# PCB-Tester-Relay-Board.net
KiCad netlist of a schematic drawn in Altium Designer
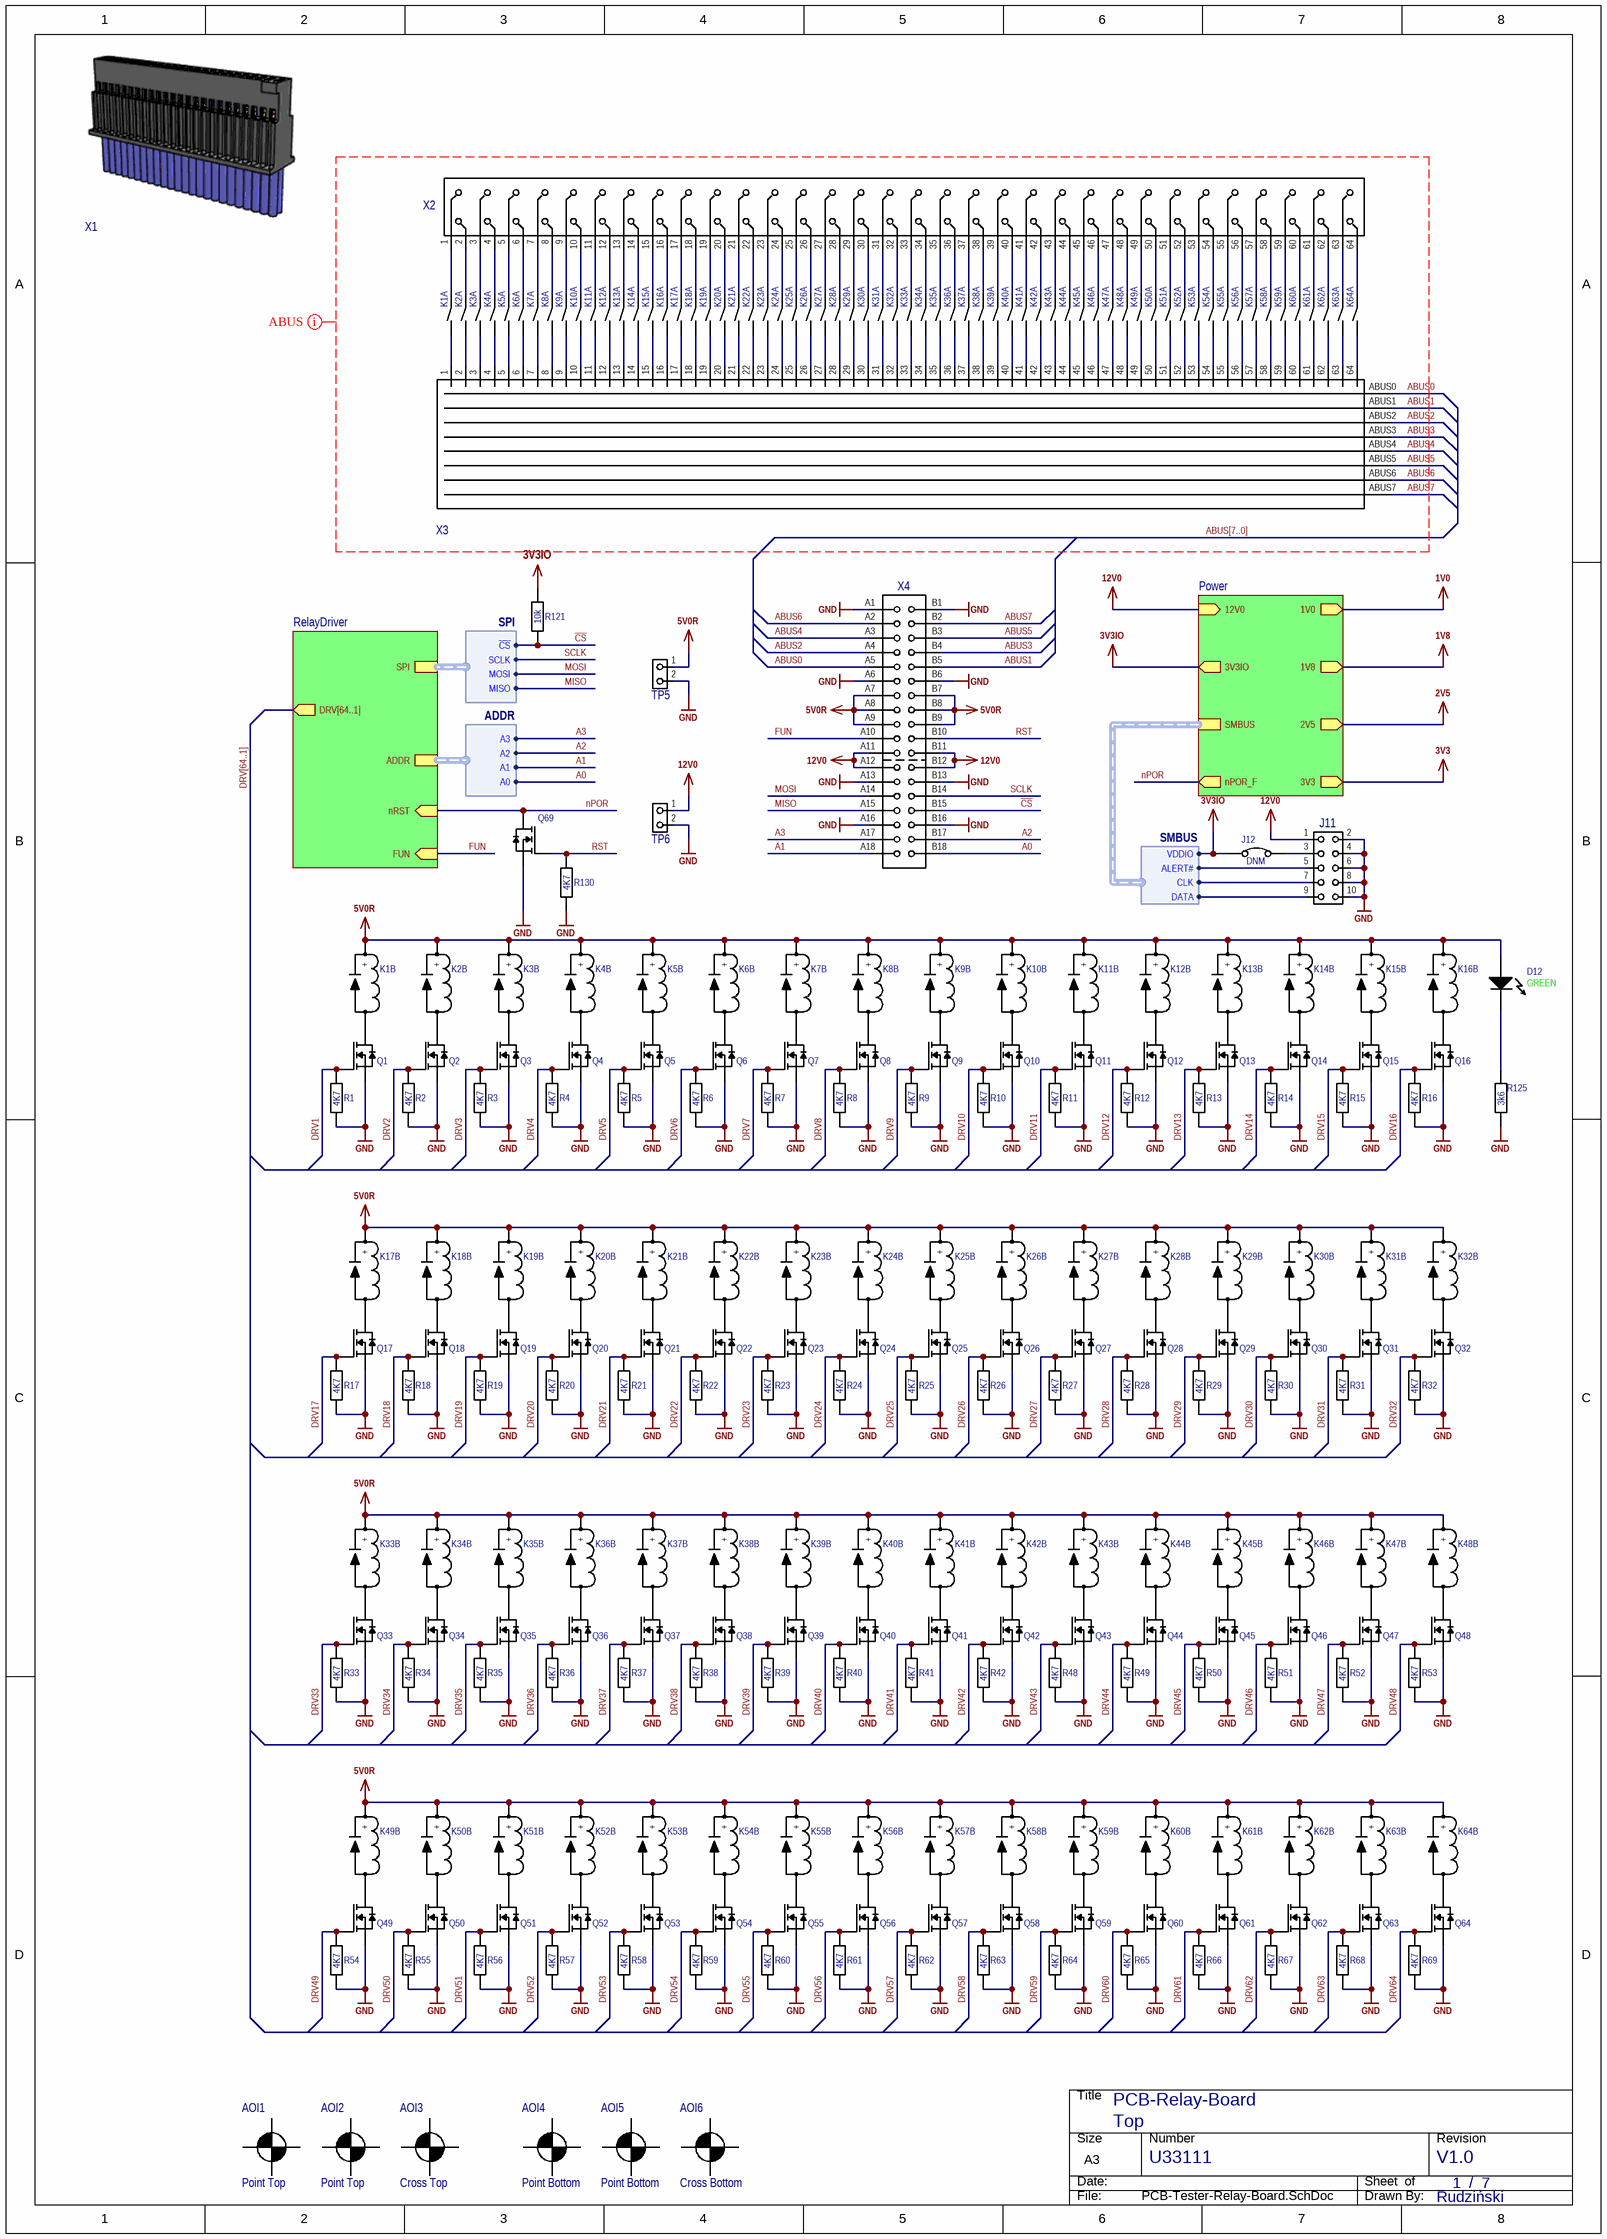
[diagram p0: PCB-Tester-Relay-Board.SchDoc]

(export (version "E")
  (design (tool "Eeschema 10.0.6"))
  (components
    (comp (ref "AOI1")
      (value "AOI")
      (footprint "Fiducial Point")
      (description "Assembly AOI")
      (fields (field (name "SHAPE") "Point Top") (field (name "13. CREATED DATE/NAME") "AUG2018/Hören"))
      (libsource (lib "chickenfood") (part "Fiducial"))
    )
    (comp (ref "AOI2")
      (value "AOI")
      (footprint "Fiducial Point")
      (description "Assembly AOI")
      (fields (field (name "SHAPE") "Point Top") (field (name "13. CREATED DATE/NAME") "AUG2018/Hören"))
      (libsource (lib "chickenfood") (part "Fiducial"))
    )
    (comp (ref "AOI3")
      (value "AOI")
      (footprint "Fiducial Cross")
      (description "Assembly AOI")
      (fields (field (name "SHAPE") "Cross Top") (field (name "13. CREATED DATE/NAME") "AUG2018/Hören"))
      (libsource (lib "chickenfood") (part "Fiducial"))
    )
    (comp (ref "AOI4")
      (value "AOI")
      (footprint "Fiducial Point")
      (description "Assembly AOI")
      (fields (field (name "SHAPE") "Point Bottom") (field (name "13. CREATED DATE/NAME") "AUG2018/Hören"))
      (libsource (lib "chickenfood") (part "Fiducial"))
    )
    (comp (ref "AOI5")
      (value "AOI")
      (footprint "Fiducial Point")
      (description "Assembly AOI")
      (fields (field (name "SHAPE") "Point Bottom") (field (name "13. CREATED DATE/NAME") "AUG2018/Hören"))
      (libsource (lib "chickenfood") (part "Fiducial"))
    )
    (comp (ref "AOI6")
      (value "AOI")
      (footprint "Fiducial Cross")
      (description "Assembly AOI")
      (fields (field (name "SHAPE") "Cross Bottom") (field (name "13. CREATED DATE/NAME") "AUG2018/Hören"))
      (libsource (lib "chickenfood") (part "Fiducial"))
    )
    (comp (ref "D12")
      (value "D")
      (footprint "L0603G")
      (description "LED GREEN DIFFUSED 0603 SMD")
      (fields
        (field (name "02. DISTRIBUTOR PART NUMBER") "475-2709-6-ND")
        (field (name "07. MANUFACTURER  PART NUMBER") "LG L29K-G2J1-24-Z")
        (field (name "COLOR") "GREEN")
        (field (name "13. CREATED DATE/NAME") "AUG2018/Hören")
      )
      (libsource (lib "chickenfood") (part "LED"))
    )
    (comp (ref "J11")
      (value "J")
      (footprint "Header 100mil 5x2")
      (description ".100\" High-Temp Variable Post Height Terminal Strip")
      (fields
        (field (name "02. DISTRIBUTOR PART NUMBER") "HMTSW-105-07-G-D-240")
        (field (name "13. CREATED DATE/NAME") "AUG2018/Hören")
      )
      (libsource (lib "PCB-Tester-Board-V1") (part "Header 5x2Pins 100mil"))
    )
    (comp (ref "J12")
      (value "DNM")
      (footprint "JumperSMD")
      (description "RES SMD 0 OHM JUMPER 1/10W 0603")
      (fields
        (field (name "02. DISTRIBUTOR PART NUMBER") "311-0.0GRDKR-ND")
        (field (name "07. MANUFACTURER  PART NUMBER") "RC0603JR-070RL")
      )
      (libsource (lib "chickenfood") (part "Jumper SMD"))
    )
    (comp (ref "K1")
      (value "K")
      (footprint "118-1A")
      (description "5V Signal Relais, Normal Open")
      (fields
        (field (name "02. DISTRIBUTOR PART NUMBER") "118-1-A-5/2D")
        (field (name "13. CREATED DATE/NAME") "20.12.17 S. Kaiser")
      )
      (libsource (lib "chickenfood") (part "118-1-A-5/2D"))
    )
    (comp (ref "K2")
      (value "K")
      (footprint "118-1A")
      (description "5V Signal Relais, Normal Open")
      (fields
        (field (name "02. DISTRIBUTOR PART NUMBER") "118-1-A-5/2D")
        (field (name "13. CREATED DATE/NAME") "20.12.17 S. Kaiser")
      )
      (libsource (lib "chickenfood") (part "118-1-A-5/2D"))
    )
    (comp (ref "K3")
      (value "K")
      (footprint "118-1A")
      (description "5V Signal Relais, Normal Open")
      (fields
        (field (name "02. DISTRIBUTOR PART NUMBER") "118-1-A-5/2D")
        (field (name "13. CREATED DATE/NAME") "20.12.17 S. Kaiser")
      )
      (libsource (lib "chickenfood") (part "118-1-A-5/2D"))
    )
    (comp (ref "K4")
      (value "K")
      (footprint "118-1A")
      (description "5V Signal Relais, Normal Open")
      (fields
        (field (name "02. DISTRIBUTOR PART NUMBER") "118-1-A-5/2D")
        (field (name "13. CREATED DATE/NAME") "20.12.17 S. Kaiser")
      )
      (libsource (lib "chickenfood") (part "118-1-A-5/2D"))
    )
    (comp (ref "K5")
      (value "K")
      (footprint "118-1A")
      (description "5V Signal Relais, Normal Open")
      (fields
        (field (name "02. DISTRIBUTOR PART NUMBER") "118-1-A-5/2D")
        (field (name "13. CREATED DATE/NAME") "20.12.17 S. Kaiser")
      )
      (libsource (lib "chickenfood") (part "118-1-A-5/2D"))
    )
    (comp (ref "K6")
      (value "K")
      (footprint "118-1A")
      (description "5V Signal Relais, Normal Open")
      (fields
        (field (name "02. DISTRIBUTOR PART NUMBER") "118-1-A-5/2D")
        (field (name "13. CREATED DATE/NAME") "20.12.17 S. Kaiser")
      )
      (libsource (lib "") (part "118-1-A-5/2D_1"))
    )
    (comp (ref "K7")
      (value "K")
      (footprint "118-1A")
      (description "5V Signal Relais, Normal Open")
      (fields
        (field (name "02. DISTRIBUTOR PART NUMBER") "118-1-A-5/2D")
        (field (name "13. CREATED DATE/NAME") "20.12.17 S. Kaiser")
      )
      (libsource (lib "chickenfood") (part "118-1-A-5/2D"))
    )
    (comp (ref "K8")
      (value "K")
      (footprint "118-1A")
      (description "5V Signal Relais, Normal Open")
      (fields
        (field (name "02. DISTRIBUTOR PART NUMBER") "118-1-A-5/2D")
        (field (name "13. CREATED DATE/NAME") "20.12.17 S. Kaiser")
      )
      (libsource (lib "chickenfood") (part "118-1-A-5/2D"))
    )
    (comp (ref "K9")
      (value "K")
      (footprint "118-1A")
      (description "5V Signal Relais, Normal Open")
      (fields
        (field (name "02. DISTRIBUTOR PART NUMBER") "118-1-A-5/2D")
        (field (name "13. CREATED DATE/NAME") "20.12.17 S. Kaiser")
      )
      (libsource (lib "") (part "118-1-A-5/2D_1"))
    )
    (comp (ref "K10")
      (value "K")
      (footprint "118-1A")
      (description "5V Signal Relais, Normal Open")
      (fields
        (field (name "02. DISTRIBUTOR PART NUMBER") "118-1-A-5/2D")
        (field (name "13. CREATED DATE/NAME") "20.12.17 S. Kaiser")
      )
      (libsource (lib "") (part "118-1-A-5/2D_1"))
    )
    (comp (ref "K11")
      (value "K")
      (footprint "118-1A")
      (description "5V Signal Relais, Normal Open")
      (fields
        (field (name "02. DISTRIBUTOR PART NUMBER") "118-1-A-5/2D")
        (field (name "13. CREATED DATE/NAME") "20.12.17 S. Kaiser")
      )
      (libsource (lib "chickenfood") (part "118-1-A-5/2D"))
    )
    (comp (ref "K12")
      (value "K")
      (footprint "118-1A")
      (description "5V Signal Relais, Normal Open")
      (fields
        (field (name "02. DISTRIBUTOR PART NUMBER") "118-1-A-5/2D")
        (field (name "13. CREATED DATE/NAME") "20.12.17 S. Kaiser")
      )
      (libsource (lib "chickenfood") (part "118-1-A-5/2D"))
    )
    (comp (ref "K13")
      (value "K")
      (footprint "118-1A")
      (description "5V Signal Relais, Normal Open")
      (fields
        (field (name "02. DISTRIBUTOR PART NUMBER") "118-1-A-5/2D")
        (field (name "13. CREATED DATE/NAME") "20.12.17 S. Kaiser")
      )
      (libsource (lib "") (part "118-1-A-5/2D_1"))
    )
    (comp (ref "K14")
      (value "K")
      (footprint "118-1A")
      (description "5V Signal Relais, Normal Open")
      (fields
        (field (name "02. DISTRIBUTOR PART NUMBER") "118-1-A-5/2D")
        (field (name "13. CREATED DATE/NAME") "20.12.17 S. Kaiser")
      )
      (libsource (lib "") (part "118-1-A-5/2D_1"))
    )
    (comp (ref "K15")
      (value "K")
      (footprint "118-1A")
      (description "5V Signal Relais, Normal Open")
      (fields
        (field (name "02. DISTRIBUTOR PART NUMBER") "118-1-A-5/2D")
        (field (name "13. CREATED DATE/NAME") "20.12.17 S. Kaiser")
      )
      (libsource (lib "chickenfood") (part "118-1-A-5/2D"))
    )
    (comp (ref "K16")
      (value "K")
      (footprint "118-1A")
      (description "5V Signal Relais, Normal Open")
      (fields
        (field (name "02. DISTRIBUTOR PART NUMBER") "118-1-A-5/2D")
        (field (name "13. CREATED DATE/NAME") "20.12.17 S. Kaiser")
      )
      (libsource (lib "") (part "118-1-A-5/2D_1"))
    )
    (comp (ref "K17")
      (value "K")
      (footprint "118-1A")
      (description "5V Signal Relais, Normal Open")
      (fields
        (field (name "02. DISTRIBUTOR PART NUMBER") "118-1-A-5/2D")
        (field (name "13. CREATED DATE/NAME") "20.12.17 S. Kaiser")
      )
      (libsource (lib "") (part "118-1-A-5/2D_1"))
    )
    (comp (ref "K18")
      (value "K")
      (footprint "118-1A")
      (description "5V Signal Relais, Normal Open")
      (fields
        (field (name "02. DISTRIBUTOR PART NUMBER") "118-1-A-5/2D")
        (field (name "13. CREATED DATE/NAME") "20.12.17 S. Kaiser")
      )
      (libsource (lib "") (part "118-1-A-5/2D_1"))
    )
    (comp (ref "K19")
      (value "K")
      (footprint "118-1A")
      (description "5V Signal Relais, Normal Open")
      (fields
        (field (name "02. DISTRIBUTOR PART NUMBER") "118-1-A-5/2D")
        (field (name "13. CREATED DATE/NAME") "20.12.17 S. Kaiser")
      )
      (libsource (lib "") (part "118-1-A-5/2D_1"))
    )
    (comp (ref "K20")
      (value "K")
      (footprint "118-1A")
      (description "5V Signal Relais, Normal Open")
      (fields
        (field (name "02. DISTRIBUTOR PART NUMBER") "118-1-A-5/2D")
        (field (name "13. CREATED DATE/NAME") "20.12.17 S. Kaiser")
      )
      (libsource (lib "chickenfood") (part "118-1-A-5/2D"))
    )
    (comp (ref "K21")
      (value "K")
      (footprint "118-1A")
      (description "5V Signal Relais, Normal Open")
      (fields
        (field (name "02. DISTRIBUTOR PART NUMBER") "118-1-A-5/2D")
        (field (name "13. CREATED DATE/NAME") "20.12.17 S. Kaiser")
      )
      (libsource (lib "") (part "118-1-A-5/2D_1"))
    )
    (comp (ref "K22")
      (value "K")
      (footprint "118-1A")
      (description "5V Signal Relais, Normal Open")
      (fields
        (field (name "02. DISTRIBUTOR PART NUMBER") "118-1-A-5/2D")
        (field (name "13. CREATED DATE/NAME") "20.12.17 S. Kaiser")
      )
      (libsource (lib "chickenfood") (part "118-1-A-5/2D"))
    )
    (comp (ref "K23")
      (value "K")
      (footprint "118-1A")
      (description "5V Signal Relais, Normal Open")
      (fields
        (field (name "02. DISTRIBUTOR PART NUMBER") "118-1-A-5/2D")
        (field (name "13. CREATED DATE/NAME") "20.12.17 S. Kaiser")
      )
      (libsource (lib "") (part "118-1-A-5/2D_1"))
    )
    (comp (ref "K24")
      (value "K")
      (footprint "118-1A")
      (description "5V Signal Relais, Normal Open")
      (fields
        (field (name "02. DISTRIBUTOR PART NUMBER") "118-1-A-5/2D")
        (field (name "13. CREATED DATE/NAME") "20.12.17 S. Kaiser")
      )
      (libsource (lib "chickenfood") (part "118-1-A-5/2D"))
    )
    (comp (ref "K25")
      (value "K")
      (footprint "118-1A")
      (description "5V Signal Relais, Normal Open")
      (fields
        (field (name "02. DISTRIBUTOR PART NUMBER") "118-1-A-5/2D")
        (field (name "13. CREATED DATE/NAME") "20.12.17 S. Kaiser")
      )
      (libsource (lib "chickenfood") (part "118-1-A-5/2D"))
    )
    (comp (ref "K26")
      (value "K")
      (footprint "118-1A")
      (description "5V Signal Relais, Normal Open")
      (fields
        (field (name "02. DISTRIBUTOR PART NUMBER") "118-1-A-5/2D")
        (field (name "13. CREATED DATE/NAME") "20.12.17 S. Kaiser")
      )
      (libsource (lib "") (part "118-1-A-5/2D_1"))
    )
    (comp (ref "K27")
      (value "K")
      (footprint "118-1A")
      (description "5V Signal Relais, Normal Open")
      (fields
        (field (name "02. DISTRIBUTOR PART NUMBER") "118-1-A-5/2D")
        (field (name "13. CREATED DATE/NAME") "20.12.17 S. Kaiser")
      )
      (libsource (lib "") (part "118-1-A-5/2D_1"))
    )
    (comp (ref "K28")
      (value "K")
      (footprint "118-1A")
      (description "5V Signal Relais, Normal Open")
      (fields
        (field (name "02. DISTRIBUTOR PART NUMBER") "118-1-A-5/2D")
        (field (name "13. CREATED DATE/NAME") "20.12.17 S. Kaiser")
      )
      (libsource (lib "chickenfood") (part "118-1-A-5/2D"))
    )
    (comp (ref "K29")
      (value "K")
      (footprint "118-1A")
      (description "5V Signal Relais, Normal Open")
      (fields
        (field (name "02. DISTRIBUTOR PART NUMBER") "118-1-A-5/2D")
        (field (name "13. CREATED DATE/NAME") "20.12.17 S. Kaiser")
      )
      (libsource (lib "") (part "118-1-A-5/2D_1"))
    )
    (comp (ref "K30")
      (value "K")
      (footprint "118-1A")
      (description "5V Signal Relais, Normal Open")
      (fields
        (field (name "02. DISTRIBUTOR PART NUMBER") "118-1-A-5/2D")
        (field (name "13. CREATED DATE/NAME") "20.12.17 S. Kaiser")
      )
      (libsource (lib "") (part "118-1-A-5/2D_1"))
    )
    (comp (ref "K31")
      (value "K")
      (footprint "118-1A")
      (description "5V Signal Relais, Normal Open")
      (fields
        (field (name "02. DISTRIBUTOR PART NUMBER") "118-1-A-5/2D")
        (field (name "13. CREATED DATE/NAME") "20.12.17 S. Kaiser")
      )
      (libsource (lib "chickenfood") (part "118-1-A-5/2D"))
    )
    (comp (ref "K32")
      (value "K")
      (footprint "118-1A")
      (description "5V Signal Relais, Normal Open")
      (fields
        (field (name "02. DISTRIBUTOR PART NUMBER") "118-1-A-5/2D")
        (field (name "13. CREATED DATE/NAME") "20.12.17 S. Kaiser")
      )
      (libsource (lib "chickenfood") (part "118-1-A-5/2D"))
    )
    (comp (ref "K33")
      (value "K")
      (footprint "118-1A")
      (description "5V Signal Relais, Normal Open")
      (fields
        (field (name "02. DISTRIBUTOR PART NUMBER") "118-1-A-5/2D")
        (field (name "13. CREATED DATE/NAME") "20.12.17 S. Kaiser")
      )
      (libsource (lib "chickenfood") (part "118-1-A-5/2D"))
    )
    (comp (ref "K34")
      (value "K")
      (footprint "118-1A")
      (description "5V Signal Relais, Normal Open")
      (fields
        (field (name "02. DISTRIBUTOR PART NUMBER") "118-1-A-5/2D")
        (field (name "13. CREATED DATE/NAME") "20.12.17 S. Kaiser")
      )
      (libsource (lib "") (part "118-1-A-5/2D_1"))
    )
    (comp (ref "K35")
      (value "K")
      (footprint "118-1A")
      (description "5V Signal Relais, Normal Open")
      (fields
        (field (name "02. DISTRIBUTOR PART NUMBER") "118-1-A-5/2D")
        (field (name "13. CREATED DATE/NAME") "20.12.17 S. Kaiser")
      )
      (libsource (lib "") (part "118-1-A-5/2D_1"))
    )
    (comp (ref "K36")
      (value "K")
      (footprint "118-1A")
      (description "5V Signal Relais, Normal Open")
      (fields
        (field (name "02. DISTRIBUTOR PART NUMBER") "118-1-A-5/2D")
        (field (name "13. CREATED DATE/NAME") "20.12.17 S. Kaiser")
      )
      (libsource (lib "") (part "118-1-A-5/2D_1"))
    )
    (comp (ref "K37")
      (value "K")
      (footprint "118-1A")
      (description "5V Signal Relais, Normal Open")
      (fields
        (field (name "02. DISTRIBUTOR PART NUMBER") "118-1-A-5/2D")
        (field (name "13. CREATED DATE/NAME") "20.12.17 S. Kaiser")
      )
      (libsource (lib "chickenfood") (part "118-1-A-5/2D"))
    )
    (comp (ref "K38")
      (value "K")
      (footprint "118-1A")
      (description "5V Signal Relais, Normal Open")
      (fields
        (field (name "02. DISTRIBUTOR PART NUMBER") "118-1-A-5/2D")
        (field (name "13. CREATED DATE/NAME") "20.12.17 S. Kaiser")
      )
      (libsource (lib "chickenfood") (part "118-1-A-5/2D"))
    )
    (comp (ref "K39")
      (value "K")
      (footprint "118-1A")
      (description "5V Signal Relais, Normal Open")
      (fields
        (field (name "02. DISTRIBUTOR PART NUMBER") "118-1-A-5/2D")
        (field (name "13. CREATED DATE/NAME") "20.12.17 S. Kaiser")
      )
      (libsource (lib "") (part "118-1-A-5/2D_1"))
    )
    (comp (ref "K40")
      (value "K")
      (footprint "118-1A")
      (description "5V Signal Relais, Normal Open")
      (fields
        (field (name "02. DISTRIBUTOR PART NUMBER") "118-1-A-5/2D")
        (field (name "13. CREATED DATE/NAME") "20.12.17 S. Kaiser")
      )
      (libsource (lib "") (part "118-1-A-5/2D_1"))
    )
    (comp (ref "K41")
      (value "K")
      (footprint "118-1A")
      (description "5V Signal Relais, Normal Open")
      (fields
        (field (name "02. DISTRIBUTOR PART NUMBER") "118-1-A-5/2D")
        (field (name "13. CREATED DATE/NAME") "20.12.17 S. Kaiser")
      )
      (libsource (lib "") (part "118-1-A-5/2D_1"))
    )
    (comp (ref "K42")
      (value "K")
      (footprint "118-1A")
      (description "5V Signal Relais, Normal Open")
      (fields
        (field (name "02. DISTRIBUTOR PART NUMBER") "118-1-A-5/2D")
        (field (name "13. CREATED DATE/NAME") "20.12.17 S. Kaiser")
      )
      (libsource (lib "") (part "118-1-A-5/2D_1"))
    )
    (comp (ref "K43")
      (value "K")
      (footprint "118-1A")
      (description "5V Signal Relais, Normal Open")
      (fields
        (field (name "02. DISTRIBUTOR PART NUMBER") "118-1-A-5/2D")
        (field (name "13. CREATED DATE/NAME") "20.12.17 S. Kaiser")
      )
      (libsource (lib "chickenfood") (part "118-1-A-5/2D"))
    )
    (comp (ref "K44")
      (value "K")
      (footprint "118-1A")
      (description "5V Signal Relais, Normal Open")
      (fields
        (field (name "02. DISTRIBUTOR PART NUMBER") "118-1-A-5/2D")
        (field (name "13. CREATED DATE/NAME") "20.12.17 S. Kaiser")
      )
      (libsource (lib "") (part "118-1-A-5/2D_1"))
    )
    (comp (ref "K45")
      (value "K")
      (footprint "118-1A")
      (description "5V Signal Relais, Normal Open")
      (fields
        (field (name "02. DISTRIBUTOR PART NUMBER") "118-1-A-5/2D")
        (field (name "13. CREATED DATE/NAME") "20.12.17 S. Kaiser")
      )
      (libsource (lib "chickenfood") (part "118-1-A-5/2D"))
    )
    (comp (ref "K46")
      (value "K")
      (footprint "118-1A")
      (description "5V Signal Relais, Normal Open")
      (fields
        (field (name "02. DISTRIBUTOR PART NUMBER") "118-1-A-5/2D")
        (field (name "13. CREATED DATE/NAME") "20.12.17 S. Kaiser")
      )
      (libsource (lib "chickenfood") (part "118-1-A-5/2D"))
    )
    (comp (ref "K47")
      (value "K")
      (footprint "118-1A")
      (description "5V Signal Relais, Normal Open")
      (fields
        (field (name "02. DISTRIBUTOR PART NUMBER") "118-1-A-5/2D")
        (field (name "13. CREATED DATE/NAME") "20.12.17 S. Kaiser")
      )
      (libsource (lib "") (part "118-1-A-5/2D_1"))
    )
    (comp (ref "K48")
      (value "K")
      (footprint "118-1A")
      (description "5V Signal Relais, Normal Open")
      (fields
        (field (name "02. DISTRIBUTOR PART NUMBER") "118-1-A-5/2D")
        (field (name "13. CREATED DATE/NAME") "20.12.17 S. Kaiser")
      )
      (libsource (lib "chickenfood") (part "118-1-A-5/2D"))
    )
    (comp (ref "K49")
      (value "K")
      (footprint "118-1A")
      (description "5V Signal Relais, Normal Open")
      (fields
        (field (name "02. DISTRIBUTOR PART NUMBER") "118-1-A-5/2D")
        (field (name "13. CREATED DATE/NAME") "20.12.17 S. Kaiser")
      )
      (libsource (lib "chickenfood") (part "118-1-A-5/2D"))
    )
    (comp (ref "K50")
      (value "K")
      (footprint "118-1A")
      (description "5V Signal Relais, Normal Open")
      (fields
        (field (name "02. DISTRIBUTOR PART NUMBER") "118-1-A-5/2D")
        (field (name "13. CREATED DATE/NAME") "20.12.17 S. Kaiser")
      )
      (libsource (lib "") (part "118-1-A-5/2D_1"))
    )
    (comp (ref "K51")
      (value "K")
      (footprint "118-1A")
      (description "5V Signal Relais, Normal Open")
      (fields
        (field (name "02. DISTRIBUTOR PART NUMBER") "118-1-A-5/2D")
        (field (name "13. CREATED DATE/NAME") "20.12.17 S. Kaiser")
      )
      (libsource (lib "") (part "118-1-A-5/2D_1"))
    )
    (comp (ref "K52")
      (value "K")
      (footprint "118-1A")
      (description "5V Signal Relais, Normal Open")
      (fields
        (field (name "02. DISTRIBUTOR PART NUMBER") "118-1-A-5/2D")
        (field (name "13. CREATED DATE/NAME") "20.12.17 S. Kaiser")
      )
      (libsource (lib "") (part "118-1-A-5/2D_1"))
    )
    (comp (ref "K53")
      (value "K")
      (footprint "118-1A")
      (description "5V Signal Relais, Normal Open")
      (fields
        (field (name "02. DISTRIBUTOR PART NUMBER") "118-1-A-5/2D")
        (field (name "13. CREATED DATE/NAME") "20.12.17 S. Kaiser")
      )
      (libsource (lib "chickenfood") (part "118-1-A-5/2D"))
    )
    (comp (ref "K54")
      (value "K")
      (footprint "118-1A")
      (description "5V Signal Relais, Normal Open")
      (fields
        (field (name "02. DISTRIBUTOR PART NUMBER") "118-1-A-5/2D")
        (field (name "13. CREATED DATE/NAME") "20.12.17 S. Kaiser")
      )
      (libsource (lib "") (part "118-1-A-5/2D_1"))
    )
    (comp (ref "K55")
      (value "K")
      (footprint "118-1A")
      (description "5V Signal Relais, Normal Open")
      (fields
        (field (name "02. DISTRIBUTOR PART NUMBER") "118-1-A-5/2D")
        (field (name "13. CREATED DATE/NAME") "20.12.17 S. Kaiser")
      )
      (libsource (lib "") (part "118-1-A-5/2D_1"))
    )
    (comp (ref "K56")
      (value "K")
      (footprint "118-1A")
      (description "5V Signal Relais, Normal Open")
      (fields
        (field (name "02. DISTRIBUTOR PART NUMBER") "118-1-A-5/2D")
        (field (name "13. CREATED DATE/NAME") "20.12.17 S. Kaiser")
      )
      (libsource (lib "") (part "118-1-A-5/2D_1"))
    )
    (comp (ref "K57")
      (value "K")
      (footprint "118-1A")
      (description "5V Signal Relais, Normal Open")
      (fields
        (field (name "02. DISTRIBUTOR PART NUMBER") "118-1-A-5/2D")
        (field (name "13. CREATED DATE/NAME") "20.12.17 S. Kaiser")
      )
      (libsource (lib "chickenfood") (part "118-1-A-5/2D"))
    )
    (comp (ref "K58")
      (value "K")
      (footprint "118-1A")
      (description "5V Signal Relais, Normal Open")
      (fields
        (field (name "02. DISTRIBUTOR PART NUMBER") "118-1-A-5/2D")
        (field (name "13. CREATED DATE/NAME") "20.12.17 S. Kaiser")
      )
      (libsource (lib "") (part "118-1-A-5/2D_1"))
    )
    (comp (ref "K59")
      (value "K")
      (footprint "118-1A")
      (description "5V Signal Relais, Normal Open")
      (fields
        (field (name "02. DISTRIBUTOR PART NUMBER") "118-1-A-5/2D")
        (field (name "13. CREATED DATE/NAME") "20.12.17 S. Kaiser")
      )
      (libsource (lib "") (part "118-1-A-5/2D_1"))
    )
    (comp (ref "K60")
      (value "K")
      (footprint "118-1A")
      (description "5V Signal Relais, Normal Open")
      (fields
        (field (name "02. DISTRIBUTOR PART NUMBER") "118-1-A-5/2D")
        (field (name "13. CREATED DATE/NAME") "20.12.17 S. Kaiser")
      )
      (libsource (lib "") (part "118-1-A-5/2D_1"))
    )
    (comp (ref "K61")
      (value "K")
      (footprint "118-1A")
      (description "5V Signal Relais, Normal Open")
      (fields
        (field (name "02. DISTRIBUTOR PART NUMBER") "118-1-A-5/2D")
        (field (name "13. CREATED DATE/NAME") "20.12.17 S. Kaiser")
      )
      (libsource (lib "chickenfood") (part "118-1-A-5/2D"))
    )
    (comp (ref "K62")
      (value "K")
      (footprint "118-1A")
      (description "5V Signal Relais, Normal Open")
      (fields
        (field (name "02. DISTRIBUTOR PART NUMBER") "118-1-A-5/2D")
        (field (name "13. CREATED DATE/NAME") "20.12.17 S. Kaiser")
      )
      (libsource (lib "") (part "118-1-A-5/2D_1"))
    )
    (comp (ref "K63")
      (value "K")
      (footprint "118-1A")
      (description "5V Signal Relais, Normal Open")
      (fields
        (field (name "02. DISTRIBUTOR PART NUMBER") "118-1-A-5/2D")
        (field (name "13. CREATED DATE/NAME") "20.12.17 S. Kaiser")
      )
      (libsource (lib "chickenfood") (part "118-1-A-5/2D"))
    )
    (comp (ref "K64")
      (value "K")
      (footprint "118-1A")
      (description "5V Signal Relais, Normal Open")
      (fields
        (field (name "02. DISTRIBUTOR PART NUMBER") "118-1-A-5/2D")
        (field (name "13. CREATED DATE/NAME") "20.12.17 S. Kaiser")
      )
      (libsource (lib "chickenfood") (part "118-1-A-5/2D"))
    )
    (comp (ref "Q1")
      (value "Q")
      (footprint "SOT23-3")
      (description "MOSFET N-CH 25V 680MA SOT-23")
      (fields
        (field (name "02. DISTRIBUTOR PART NUMBER") "FDV303NDKR-ND")
        (field (name "07. MANUFACTURER  PART NUMBER") "FDV303N")
        (field (name "13. CREATED DATE/NAME") "AUG 2018 / Hören")
      )
      (libsource (lib "SCT8-Board1") (part "FDV303N"))
    )
    (comp (ref "Q2")
      (value "Q")
      (footprint "SOT23-3")
      (description "MOSFET N-CH 25V 680MA SOT-23")
      (fields
        (field (name "02. DISTRIBUTOR PART NUMBER") "FDV303NDKR-ND")
        (field (name "07. MANUFACTURER  PART NUMBER") "FDV303N")
        (field (name "13. CREATED DATE/NAME") "AUG 2018 / Hören")
      )
      (libsource (lib "SCT8-Board1") (part "FDV303N"))
    )
    (comp (ref "Q3")
      (value "Q")
      (footprint "SOT23-3")
      (description "MOSFET N-CH 25V 680MA SOT-23")
      (fields
        (field (name "02. DISTRIBUTOR PART NUMBER") "FDV303NDKR-ND")
        (field (name "07. MANUFACTURER  PART NUMBER") "FDV303N")
        (field (name "13. CREATED DATE/NAME") "AUG 2018 / Hören")
      )
      (libsource (lib "SCT8-Board1") (part "FDV303N"))
    )
    (comp (ref "Q4")
      (value "Q")
      (footprint "SOT23-3")
      (description "MOSFET N-CH 25V 680MA SOT-23")
      (fields
        (field (name "02. DISTRIBUTOR PART NUMBER") "FDV303NDKR-ND")
        (field (name "07. MANUFACTURER  PART NUMBER") "FDV303N")
        (field (name "13. CREATED DATE/NAME") "AUG 2018 / Hören")
      )
      (libsource (lib "SCT8-Board1") (part "FDV303N"))
    )
    (comp (ref "Q5")
      (value "Q")
      (footprint "SOT23-3")
      (description "MOSFET N-CH 25V 680MA SOT-23")
      (fields
        (field (name "02. DISTRIBUTOR PART NUMBER") "FDV303NDKR-ND")
        (field (name "07. MANUFACTURER  PART NUMBER") "FDV303N")
        (field (name "13. CREATED DATE/NAME") "AUG 2018 / Hören")
      )
      (libsource (lib "SCT8-Board1") (part "FDV303N"))
    )
    (comp (ref "Q6")
      (value "Q")
      (footprint "SOT23-3")
      (description "MOSFET N-CH 25V 680MA SOT-23")
      (fields
        (field (name "02. DISTRIBUTOR PART NUMBER") "FDV303NDKR-ND")
        (field (name "07. MANUFACTURER  PART NUMBER") "FDV303N")
        (field (name "13. CREATED DATE/NAME") "AUG 2018 / Hören")
      )
      (libsource (lib "SCT8-Board1") (part "FDV303N"))
    )
    (comp (ref "Q7")
      (value "Q")
      (footprint "SOT23-3")
      (description "MOSFET N-CH 25V 680MA SOT-23")
      (fields
        (field (name "02. DISTRIBUTOR PART NUMBER") "FDV303NDKR-ND")
        (field (name "07. MANUFACTURER  PART NUMBER") "FDV303N")
        (field (name "13. CREATED DATE/NAME") "AUG 2018 / Hören")
      )
      (libsource (lib "SCT8-Board1") (part "FDV303N"))
    )
    (comp (ref "Q8")
      (value "Q")
      (footprint "SOT23-3")
      (description "MOSFET N-CH 25V 680MA SOT-23")
      (fields
        (field (name "02. DISTRIBUTOR PART NUMBER") "FDV303NDKR-ND")
        (field (name "07. MANUFACTURER  PART NUMBER") "FDV303N")
        (field (name "13. CREATED DATE/NAME") "AUG 2018 / Hören")
      )
      (libsource (lib "SCT8-Board1") (part "FDV303N"))
    )
    (comp (ref "Q9")
      (value "Q")
      (footprint "SOT23-3")
      (description "MOSFET N-CH 25V 680MA SOT-23")
      (fields
        (field (name "02. DISTRIBUTOR PART NUMBER") "FDV303NDKR-ND")
        (field (name "07. MANUFACTURER  PART NUMBER") "FDV303N")
        (field (name "13. CREATED DATE/NAME") "AUG 2018 / Hören")
      )
      (libsource (lib "SCT8-Board1") (part "FDV303N"))
    )
    (comp (ref "Q10")
      (value "Q")
      (footprint "SOT23-3")
      (description "MOSFET N-CH 25V 680MA SOT-23")
      (fields
        (field (name "02. DISTRIBUTOR PART NUMBER") "FDV303NDKR-ND")
        (field (name "07. MANUFACTURER  PART NUMBER") "FDV303N")
        (field (name "13. CREATED DATE/NAME") "AUG 2018 / Hören")
      )
      (libsource (lib "SCT8-Board1") (part "FDV303N"))
    )
    (comp (ref "Q11")
      (value "Q")
      (footprint "SOT23-3")
      (description "MOSFET N-CH 25V 680MA SOT-23")
      (fields
        (field (name "02. DISTRIBUTOR PART NUMBER") "FDV303NDKR-ND")
        (field (name "07. MANUFACTURER  PART NUMBER") "FDV303N")
        (field (name "13. CREATED DATE/NAME") "AUG 2018 / Hören")
      )
      (libsource (lib "SCT8-Board1") (part "FDV303N"))
    )
    (comp (ref "Q12")
      (value "Q")
      (footprint "SOT23-3")
      (description "MOSFET N-CH 25V 680MA SOT-23")
      (fields
        (field (name "02. DISTRIBUTOR PART NUMBER") "FDV303NDKR-ND")
        (field (name "07. MANUFACTURER  PART NUMBER") "FDV303N")
        (field (name "13. CREATED DATE/NAME") "AUG 2018 / Hören")
      )
      (libsource (lib "SCT8-Board1") (part "FDV303N"))
    )
    (comp (ref "Q13")
      (value "Q")
      (footprint "SOT23-3")
      (description "MOSFET N-CH 25V 680MA SOT-23")
      (fields
        (field (name "02. DISTRIBUTOR PART NUMBER") "FDV303NDKR-ND")
        (field (name "07. MANUFACTURER  PART NUMBER") "FDV303N")
        (field (name "13. CREATED DATE/NAME") "AUG 2018 / Hören")
      )
      (libsource (lib "SCT8-Board1") (part "FDV303N"))
    )
    (comp (ref "Q14")
      (value "Q")
      (footprint "SOT23-3")
      (description "MOSFET N-CH 25V 680MA SOT-23")
      (fields
        (field (name "02. DISTRIBUTOR PART NUMBER") "FDV303NDKR-ND")
        (field (name "07. MANUFACTURER  PART NUMBER") "FDV303N")
        (field (name "13. CREATED DATE/NAME") "AUG 2018 / Hören")
      )
      (libsource (lib "SCT8-Board1") (part "FDV303N"))
    )
    (comp (ref "Q15")
      (value "Q")
      (footprint "SOT23-3")
      (description "MOSFET N-CH 25V 680MA SOT-23")
      (fields
        (field (name "02. DISTRIBUTOR PART NUMBER") "FDV303NDKR-ND")
        (field (name "07. MANUFACTURER  PART NUMBER") "FDV303N")
        (field (name "13. CREATED DATE/NAME") "AUG 2018 / Hören")
      )
      (libsource (lib "SCT8-Board1") (part "FDV303N"))
    )
    (comp (ref "Q16")
      (value "Q")
      (footprint "SOT23-3")
      (description "MOSFET N-CH 25V 680MA SOT-23")
      (fields
        (field (name "02. DISTRIBUTOR PART NUMBER") "FDV303NDKR-ND")
        (field (name "07. MANUFACTURER  PART NUMBER") "FDV303N")
        (field (name "13. CREATED DATE/NAME") "AUG 2018 / Hören")
      )
      (libsource (lib "SCT8-Board1") (part "FDV303N"))
    )
    (comp (ref "Q17")
      (value "Q")
      (footprint "SOT23-3")
      (description "MOSFET N-CH 25V 680MA SOT-23")
      (fields
        (field (name "02. DISTRIBUTOR PART NUMBER") "FDV303NDKR-ND")
        (field (name "07. MANUFACTURER  PART NUMBER") "FDV303N")
        (field (name "13. CREATED DATE/NAME") "AUG 2018 / Hören")
      )
      (libsource (lib "SCT8-Board1") (part "FDV303N"))
    )
    (comp (ref "Q18")
      (value "Q")
      (footprint "SOT23-3")
      (description "MOSFET N-CH 25V 680MA SOT-23")
      (fields
        (field (name "02. DISTRIBUTOR PART NUMBER") "FDV303NDKR-ND")
        (field (name "07. MANUFACTURER  PART NUMBER") "FDV303N")
        (field (name "13. CREATED DATE/NAME") "AUG 2018 / Hören")
      )
      (libsource (lib "SCT8-Board1") (part "FDV303N"))
    )
    (comp (ref "Q19")
      (value "Q")
      (footprint "SOT23-3")
      (description "MOSFET N-CH 25V 680MA SOT-23")
      (fields
        (field (name "02. DISTRIBUTOR PART NUMBER") "FDV303NDKR-ND")
        (field (name "07. MANUFACTURER  PART NUMBER") "FDV303N")
        (field (name "13. CREATED DATE/NAME") "AUG 2018 / Hören")
      )
      (libsource (lib "SCT8-Board1") (part "FDV303N"))
    )
    (comp (ref "Q20")
      (value "Q")
      (footprint "SOT23-3")
      (description "MOSFET N-CH 25V 680MA SOT-23")
      (fields
        (field (name "02. DISTRIBUTOR PART NUMBER") "FDV303NDKR-ND")
        (field (name "07. MANUFACTURER  PART NUMBER") "FDV303N")
        (field (name "13. CREATED DATE/NAME") "AUG 2018 / Hören")
      )
      (libsource (lib "SCT8-Board1") (part "FDV303N"))
    )
    (comp (ref "Q21")
      (value "Q")
      (footprint "SOT23-3")
      (description "MOSFET N-CH 25V 680MA SOT-23")
      (fields
        (field (name "02. DISTRIBUTOR PART NUMBER") "FDV303NDKR-ND")
        (field (name "07. MANUFACTURER  PART NUMBER") "FDV303N")
        (field (name "13. CREATED DATE/NAME") "AUG 2018 / Hören")
      )
      (libsource (lib "SCT8-Board1") (part "FDV303N"))
    )
    (comp (ref "Q22")
      (value "Q")
      (footprint "SOT23-3")
      (description "MOSFET N-CH 25V 680MA SOT-23")
      (fields
        (field (name "02. DISTRIBUTOR PART NUMBER") "FDV303NDKR-ND")
        (field (name "07. MANUFACTURER  PART NUMBER") "FDV303N")
        (field (name "13. CREATED DATE/NAME") "AUG 2018 / Hören")
      )
      (libsource (lib "SCT8-Board1") (part "FDV303N"))
    )
    (comp (ref "Q23")
      (value "Q")
      (footprint "SOT23-3")
      (description "MOSFET N-CH 25V 680MA SOT-23")
      (fields
        (field (name "02. DISTRIBUTOR PART NUMBER") "FDV303NDKR-ND")
        (field (name "07. MANUFACTURER  PART NUMBER") "FDV303N")
        (field (name "13. CREATED DATE/NAME") "AUG 2018 / Hören")
      )
      (libsource (lib "SCT8-Board1") (part "FDV303N"))
    )
    (comp (ref "Q24")
      (value "Q")
      (footprint "SOT23-3")
      (description "MOSFET N-CH 25V 680MA SOT-23")
      (fields
        (field (name "02. DISTRIBUTOR PART NUMBER") "FDV303NDKR-ND")
        (field (name "07. MANUFACTURER  PART NUMBER") "FDV303N")
        (field (name "13. CREATED DATE/NAME") "AUG 2018 / Hören")
      )
      (libsource (lib "SCT8-Board1") (part "FDV303N"))
    )
    (comp (ref "Q25")
      (value "Q")
      (footprint "SOT23-3")
      (description "MOSFET N-CH 25V 680MA SOT-23")
      (fields
        (field (name "02. DISTRIBUTOR PART NUMBER") "FDV303NDKR-ND")
        (field (name "07. MANUFACTURER  PART NUMBER") "FDV303N")
        (field (name "13. CREATED DATE/NAME") "AUG 2018 / Hören")
      )
      (libsource (lib "SCT8-Board1") (part "FDV303N"))
    )
    (comp (ref "Q26")
      (value "Q")
      (footprint "SOT23-3")
      (description "MOSFET N-CH 25V 680MA SOT-23")
      (fields
        (field (name "02. DISTRIBUTOR PART NUMBER") "FDV303NDKR-ND")
        (field (name "07. MANUFACTURER  PART NUMBER") "FDV303N")
        (field (name "13. CREATED DATE/NAME") "AUG 2018 / Hören")
      )
      (libsource (lib "SCT8-Board1") (part "FDV303N"))
    )
    (comp (ref "Q27")
      (value "Q")
      (footprint "SOT23-3")
      (description "MOSFET N-CH 25V 680MA SOT-23")
      (fields
        (field (name "02. DISTRIBUTOR PART NUMBER") "FDV303NDKR-ND")
        (field (name "07. MANUFACTURER  PART NUMBER") "FDV303N")
        (field (name "13. CREATED DATE/NAME") "AUG 2018 / Hören")
      )
      (libsource (lib "SCT8-Board1") (part "FDV303N"))
    )
    (comp (ref "Q28")
      (value "Q")
      (footprint "SOT23-3")
      (description "MOSFET N-CH 25V 680MA SOT-23")
      (fields
        (field (name "02. DISTRIBUTOR PART NUMBER") "FDV303NDKR-ND")
        (field (name "07. MANUFACTURER  PART NUMBER") "FDV303N")
        (field (name "13. CREATED DATE/NAME") "AUG 2018 / Hören")
      )
      (libsource (lib "SCT8-Board1") (part "FDV303N"))
    )
    (comp (ref "Q29")
      (value "Q")
      (footprint "SOT23-3")
      (description "MOSFET N-CH 25V 680MA SOT-23")
      (fields
        (field (name "02. DISTRIBUTOR PART NUMBER") "FDV303NDKR-ND")
        (field (name "07. MANUFACTURER  PART NUMBER") "FDV303N")
        (field (name "13. CREATED DATE/NAME") "AUG 2018 / Hören")
      )
      (libsource (lib "SCT8-Board1") (part "FDV303N"))
    )
    (comp (ref "Q30")
      (value "Q")
      (footprint "SOT23-3")
      (description "MOSFET N-CH 25V 680MA SOT-23")
      (fields
        (field (name "02. DISTRIBUTOR PART NUMBER") "FDV303NDKR-ND")
        (field (name "07. MANUFACTURER  PART NUMBER") "FDV303N")
        (field (name "13. CREATED DATE/NAME") "AUG 2018 / Hören")
      )
      (libsource (lib "SCT8-Board1") (part "FDV303N"))
    )
    (comp (ref "Q31")
      (value "Q")
      (footprint "SOT23-3")
      (description "MOSFET N-CH 25V 680MA SOT-23")
      (fields
        (field (name "02. DISTRIBUTOR PART NUMBER") "FDV303NDKR-ND")
        (field (name "07. MANUFACTURER  PART NUMBER") "FDV303N")
        (field (name "13. CREATED DATE/NAME") "AUG 2018 / Hören")
      )
      (libsource (lib "SCT8-Board1") (part "FDV303N"))
    )
    (comp (ref "Q32")
      (value "Q")
      (footprint "SOT23-3")
      (description "MOSFET N-CH 25V 680MA SOT-23")
      (fields
        (field (name "02. DISTRIBUTOR PART NUMBER") "FDV303NDKR-ND")
        (field (name "07. MANUFACTURER  PART NUMBER") "FDV303N")
        (field (name "13. CREATED DATE/NAME") "AUG 2018 / Hören")
      )
      (libsource (lib "SCT8-Board1") (part "FDV303N"))
    )
    (comp (ref "Q33")
      (value "Q")
      (footprint "SOT23-3")
      (description "MOSFET N-CH 25V 680MA SOT-23")
      (fields
        (field (name "02. DISTRIBUTOR PART NUMBER") "FDV303NDKR-ND")
        (field (name "07. MANUFACTURER  PART NUMBER") "FDV303N")
        (field (name "13. CREATED DATE/NAME") "AUG 2018 / Hören")
      )
      (libsource (lib "SCT8-Board1") (part "FDV303N"))
    )
    (comp (ref "Q34")
      (value "Q")
      (footprint "SOT23-3")
      (description "MOSFET N-CH 25V 680MA SOT-23")
      (fields
        (field (name "02. DISTRIBUTOR PART NUMBER") "FDV303NDKR-ND")
        (field (name "07. MANUFACTURER  PART NUMBER") "FDV303N")
        (field (name "13. CREATED DATE/NAME") "AUG 2018 / Hören")
      )
      (libsource (lib "SCT8-Board1") (part "FDV303N"))
    )
    (comp (ref "Q35")
      (value "Q")
      (footprint "SOT23-3")
      (description "MOSFET N-CH 25V 680MA SOT-23")
      (fields
        (field (name "02. DISTRIBUTOR PART NUMBER") "FDV303NDKR-ND")
        (field (name "07. MANUFACTURER  PART NUMBER") "FDV303N")
        (field (name "13. CREATED DATE/NAME") "AUG 2018 / Hören")
      )
      (libsource (lib "SCT8-Board1") (part "FDV303N"))
    )
    (comp (ref "Q36")
      (value "Q")
      (footprint "SOT23-3")
      (description "MOSFET N-CH 25V 680MA SOT-23")
      (fields
        (field (name "02. DISTRIBUTOR PART NUMBER") "FDV303NDKR-ND")
        (field (name "07. MANUFACTURER  PART NUMBER") "FDV303N")
        (field (name "13. CREATED DATE/NAME") "AUG 2018 / Hören")
      )
      (libsource (lib "SCT8-Board1") (part "FDV303N"))
    )
    (comp (ref "Q37")
      (value "Q")
      (footprint "SOT23-3")
      (description "MOSFET N-CH 25V 680MA SOT-23")
      (fields
        (field (name "02. DISTRIBUTOR PART NUMBER") "FDV303NDKR-ND")
        (field (name "07. MANUFACTURER  PART NUMBER") "FDV303N")
        (field (name "13. CREATED DATE/NAME") "AUG 2018 / Hören")
      )
      (libsource (lib "SCT8-Board1") (part "FDV303N"))
    )
    (comp (ref "Q38")
      (value "Q")
      (footprint "SOT23-3")
      (description "MOSFET N-CH 25V 680MA SOT-23")
      (fields
        (field (name "02. DISTRIBUTOR PART NUMBER") "FDV303NDKR-ND")
        (field (name "07. MANUFACTURER  PART NUMBER") "FDV303N")
        (field (name "13. CREATED DATE/NAME") "AUG 2018 / Hören")
      )
      (libsource (lib "SCT8-Board1") (part "FDV303N"))
    )
    (comp (ref "Q39")
      (value "Q")
      (footprint "SOT23-3")
      (description "MOSFET N-CH 25V 680MA SOT-23")
      (fields
        (field (name "02. DISTRIBUTOR PART NUMBER") "FDV303NDKR-ND")
        (field (name "07. MANUFACTURER  PART NUMBER") "FDV303N")
        (field (name "13. CREATED DATE/NAME") "AUG 2018 / Hören")
      )
      (libsource (lib "SCT8-Board1") (part "FDV303N"))
    )
    (comp (ref "Q40")
      (value "Q")
      (footprint "SOT23-3")
      (description "MOSFET N-CH 25V 680MA SOT-23")
      (fields
        (field (name "02. DISTRIBUTOR PART NUMBER") "FDV303NDKR-ND")
        (field (name "07. MANUFACTURER  PART NUMBER") "FDV303N")
        (field (name "13. CREATED DATE/NAME") "AUG 2018 / Hören")
      )
      (libsource (lib "SCT8-Board1") (part "FDV303N"))
    )
    (comp (ref "Q41")
      (value "Q")
      (footprint "SOT23-3")
      (description "MOSFET N-CH 25V 680MA SOT-23")
      (fields
        (field (name "02. DISTRIBUTOR PART NUMBER") "FDV303NDKR-ND")
        (field (name "07. MANUFACTURER  PART NUMBER") "FDV303N")
        (field (name "13. CREATED DATE/NAME") "AUG 2018 / Hören")
      )
      (libsource (lib "SCT8-Board1") (part "FDV303N"))
    )
    (comp (ref "Q42")
      (value "Q")
      (footprint "SOT23-3")
      (description "MOSFET N-CH 25V 680MA SOT-23")
      (fields
        (field (name "02. DISTRIBUTOR PART NUMBER") "FDV303NDKR-ND")
        (field (name "07. MANUFACTURER  PART NUMBER") "FDV303N")
        (field (name "13. CREATED DATE/NAME") "AUG 2018 / Hören")
      )
      (libsource (lib "SCT8-Board1") (part "FDV303N"))
    )
    (comp (ref "Q43")
      (value "Q")
      (footprint "SOT23-3")
      (description "MOSFET N-CH 25V 680MA SOT-23")
      (fields
        (field (name "02. DISTRIBUTOR PART NUMBER") "FDV303NDKR-ND")
        (field (name "07. MANUFACTURER  PART NUMBER") "FDV303N")
        (field (name "13. CREATED DATE/NAME") "AUG 2018 / Hören")
      )
      (libsource (lib "SCT8-Board1") (part "FDV303N"))
    )
    (comp (ref "Q44")
      (value "Q")
      (footprint "SOT23-3")
      (description "MOSFET N-CH 25V 680MA SOT-23")
      (fields
        (field (name "02. DISTRIBUTOR PART NUMBER") "FDV303NDKR-ND")
        (field (name "07. MANUFACTURER  PART NUMBER") "FDV303N")
        (field (name "13. CREATED DATE/NAME") "AUG 2018 / Hören")
      )
      (libsource (lib "SCT8-Board1") (part "FDV303N"))
    )
    (comp (ref "Q45")
      (value "Q")
      (footprint "SOT23-3")
      (description "MOSFET N-CH 25V 680MA SOT-23")
      (fields
        (field (name "02. DISTRIBUTOR PART NUMBER") "FDV303NDKR-ND")
        (field (name "07. MANUFACTURER  PART NUMBER") "FDV303N")
        (field (name "13. CREATED DATE/NAME") "AUG 2018 / Hören")
      )
      (libsource (lib "SCT8-Board1") (part "FDV303N"))
    )
    (comp (ref "Q46")
      (value "Q")
      (footprint "SOT23-3")
      (description "MOSFET N-CH 25V 680MA SOT-23")
      (fields
        (field (name "02. DISTRIBUTOR PART NUMBER") "FDV303NDKR-ND")
        (field (name "07. MANUFACTURER  PART NUMBER") "FDV303N")
        (field (name "13. CREATED DATE/NAME") "AUG 2018 / Hören")
      )
      (libsource (lib "SCT8-Board1") (part "FDV303N"))
    )
    (comp (ref "Q47")
      (value "Q")
      (footprint "SOT23-3")
      (description "MOSFET N-CH 25V 680MA SOT-23")
      (fields
        (field (name "02. DISTRIBUTOR PART NUMBER") "FDV303NDKR-ND")
        (field (name "07. MANUFACTURER  PART NUMBER") "FDV303N")
        (field (name "13. CREATED DATE/NAME") "AUG 2018 / Hören")
      )
      (libsource (lib "SCT8-Board1") (part "FDV303N"))
    )
    (comp (ref "Q48")
      (value "Q")
      (footprint "SOT23-3")
      (description "MOSFET N-CH 25V 680MA SOT-23")
      (fields
        (field (name "02. DISTRIBUTOR PART NUMBER") "FDV303NDKR-ND")
        (field (name "07. MANUFACTURER  PART NUMBER") "FDV303N")
        (field (name "13. CREATED DATE/NAME") "AUG 2018 / Hören")
      )
      (libsource (lib "SCT8-Board1") (part "FDV303N"))
    )
    (comp (ref "Q49")
      (value "Q")
      (footprint "SOT23-3")
      (description "MOSFET N-CH 25V 680MA SOT-23")
      (fields
        (field (name "02. DISTRIBUTOR PART NUMBER") "FDV303NDKR-ND")
        (field (name "07. MANUFACTURER  PART NUMBER") "FDV303N")
        (field (name "13. CREATED DATE/NAME") "AUG 2018 / Hören")
      )
      (libsource (lib "SCT8-Board1") (part "FDV303N"))
    )
    (comp (ref "Q50")
      (value "Q")
      (footprint "SOT23-3")
      (description "MOSFET N-CH 25V 680MA SOT-23")
      (fields
        (field (name "02. DISTRIBUTOR PART NUMBER") "FDV303NDKR-ND")
        (field (name "07. MANUFACTURER  PART NUMBER") "FDV303N")
        (field (name "13. CREATED DATE/NAME") "AUG 2018 / Hören")
      )
      (libsource (lib "SCT8-Board1") (part "FDV303N"))
    )
    (comp (ref "Q51")
      (value "Q")
      (footprint "SOT23-3")
      (description "MOSFET N-CH 25V 680MA SOT-23")
      (fields
        (field (name "02. DISTRIBUTOR PART NUMBER") "FDV303NDKR-ND")
        (field (name "07. MANUFACTURER  PART NUMBER") "FDV303N")
        (field (name "13. CREATED DATE/NAME") "AUG 2018 / Hören")
      )
      (libsource (lib "SCT8-Board1") (part "FDV303N"))
    )
    (comp (ref "Q52")
      (value "Q")
      (footprint "SOT23-3")
      (description "MOSFET N-CH 25V 680MA SOT-23")
      (fields
        (field (name "02. DISTRIBUTOR PART NUMBER") "FDV303NDKR-ND")
        (field (name "07. MANUFACTURER  PART NUMBER") "FDV303N")
        (field (name "13. CREATED DATE/NAME") "AUG 2018 / Hören")
      )
      (libsource (lib "SCT8-Board1") (part "FDV303N"))
    )
    (comp (ref "Q53")
      (value "Q")
      (footprint "SOT23-3")
      (description "MOSFET N-CH 25V 680MA SOT-23")
      (fields
        (field (name "02. DISTRIBUTOR PART NUMBER") "FDV303NDKR-ND")
        (field (name "07. MANUFACTURER  PART NUMBER") "FDV303N")
        (field (name "13. CREATED DATE/NAME") "AUG 2018 / Hören")
      )
      (libsource (lib "SCT8-Board1") (part "FDV303N"))
    )
    (comp (ref "Q54")
      (value "Q")
      (footprint "SOT23-3")
      (description "MOSFET N-CH 25V 680MA SOT-23")
      (fields
        (field (name "02. DISTRIBUTOR PART NUMBER") "FDV303NDKR-ND")
        (field (name "07. MANUFACTURER  PART NUMBER") "FDV303N")
        (field (name "13. CREATED DATE/NAME") "AUG 2018 / Hören")
      )
      (libsource (lib "SCT8-Board1") (part "FDV303N"))
    )
    (comp (ref "Q55")
      (value "Q")
      (footprint "SOT23-3")
      (description "MOSFET N-CH 25V 680MA SOT-23")
      (fields
        (field (name "02. DISTRIBUTOR PART NUMBER") "FDV303NDKR-ND")
        (field (name "07. MANUFACTURER  PART NUMBER") "FDV303N")
        (field (name "13. CREATED DATE/NAME") "AUG 2018 / Hören")
      )
      (libsource (lib "SCT8-Board1") (part "FDV303N"))
    )
    (comp (ref "Q56")
      (value "Q")
      (footprint "SOT23-3")
      (description "MOSFET N-CH 25V 680MA SOT-23")
      (fields
        (field (name "02. DISTRIBUTOR PART NUMBER") "FDV303NDKR-ND")
        (field (name "07. MANUFACTURER  PART NUMBER") "FDV303N")
        (field (name "13. CREATED DATE/NAME") "AUG 2018 / Hören")
      )
      (libsource (lib "SCT8-Board1") (part "FDV303N"))
    )
    (comp (ref "Q57")
      (value "Q")
      (footprint "SOT23-3")
      (description "MOSFET N-CH 25V 680MA SOT-23")
      (fields
        (field (name "02. DISTRIBUTOR PART NUMBER") "FDV303NDKR-ND")
        (field (name "07. MANUFACTURER  PART NUMBER") "FDV303N")
        (field (name "13. CREATED DATE/NAME") "AUG 2018 / Hören")
      )
      (libsource (lib "SCT8-Board1") (part "FDV303N"))
    )
    (comp (ref "Q58")
      (value "Q")
      (footprint "SOT23-3")
      (description "MOSFET N-CH 25V 680MA SOT-23")
      (fields
        (field (name "02. DISTRIBUTOR PART NUMBER") "FDV303NDKR-ND")
        (field (name "07. MANUFACTURER  PART NUMBER") "FDV303N")
        (field (name "13. CREATED DATE/NAME") "AUG 2018 / Hören")
      )
      (libsource (lib "SCT8-Board1") (part "FDV303N"))
    )
    (comp (ref "Q59")
      (value "Q")
      (footprint "SOT23-3")
      (description "MOSFET N-CH 25V 680MA SOT-23")
      (fields
        (field (name "02. DISTRIBUTOR PART NUMBER") "FDV303NDKR-ND")
        (field (name "07. MANUFACTURER  PART NUMBER") "FDV303N")
        (field (name "13. CREATED DATE/NAME") "AUG 2018 / Hören")
      )
      (libsource (lib "SCT8-Board1") (part "FDV303N"))
    )
    (comp (ref "Q60")
      (value "Q")
      (footprint "SOT23-3")
      (description "MOSFET N-CH 25V 680MA SOT-23")
      (fields
        (field (name "02. DISTRIBUTOR PART NUMBER") "FDV303NDKR-ND")
        (field (name "07. MANUFACTURER  PART NUMBER") "FDV303N")
        (field (name "13. CREATED DATE/NAME") "AUG 2018 / Hören")
      )
      (libsource (lib "SCT8-Board1") (part "FDV303N"))
    )
    (comp (ref "Q61")
      (value "Q")
      (footprint "SOT23-3")
      (description "MOSFET N-CH 25V 680MA SOT-23")
      (fields
        (field (name "02. DISTRIBUTOR PART NUMBER") "FDV303NDKR-ND")
        (field (name "07. MANUFACTURER  PART NUMBER") "FDV303N")
        (field (name "13. CREATED DATE/NAME") "AUG 2018 / Hören")
      )
      (libsource (lib "SCT8-Board1") (part "FDV303N"))
    )
    (comp (ref "Q62")
      (value "Q")
      (footprint "SOT23-3")
      (description "MOSFET N-CH 25V 680MA SOT-23")
      (fields
        (field (name "02. DISTRIBUTOR PART NUMBER") "FDV303NDKR-ND")
        (field (name "07. MANUFACTURER  PART NUMBER") "FDV303N")
        (field (name "13. CREATED DATE/NAME") "AUG 2018 / Hören")
      )
      (libsource (lib "SCT8-Board1") (part "FDV303N"))
    )
    (comp (ref "Q63")
      (value "Q")
      (footprint "SOT23-3")
      (description "MOSFET N-CH 25V 680MA SOT-23")
      (fields
        (field (name "02. DISTRIBUTOR PART NUMBER") "FDV303NDKR-ND")
        (field (name "07. MANUFACTURER  PART NUMBER") "FDV303N")
        (field (name "13. CREATED DATE/NAME") "AUG 2018 / Hören")
      )
      (libsource (lib "SCT8-Board1") (part "FDV303N"))
    )
    (comp (ref "Q64")
      (value "Q")
      (footprint "SOT23-3")
      (description "MOSFET N-CH 25V 680MA SOT-23")
      (fields
        (field (name "02. DISTRIBUTOR PART NUMBER") "FDV303NDKR-ND")
        (field (name "07. MANUFACTURER  PART NUMBER") "FDV303N")
        (field (name "13. CREATED DATE/NAME") "AUG 2018 / Hören")
      )
      (libsource (lib "SCT8-Board1") (part "FDV303N"))
    )
    (comp (ref "Q69")
      (value "Q")
      (footprint "SOT23-3")
      (description "MOSFET N-CH 25V 680MA SOT-23")
      (fields
        (field (name "02. DISTRIBUTOR PART NUMBER") "FDV303NDKR-ND")
        (field (name "07. MANUFACTURER  PART NUMBER") "FDV303N")
        (field (name "13. CREATED DATE/NAME") "AUG 2018 / Hören")
      )
      (libsource (lib "SCT8-Board1") (part "FDV303N"))
    )
    (comp (ref "R1")
      (value "4K7")
      (footprint "R0402 Reflow")
      (description "RES SMD 4.7K OHM 1% 1/16W 0402")
      (fields
        (field (name "TOLERANCE") "±1%")
        (field (name "02. DISTRIBUTOR PART NUMBER") "311-4.7KLRDKR-ND")
        (field (name "13. CREATED DATE/NAME") "AUG2018/Hören")
      )
      (libsource (lib "chickenfood") (part "R"))
    )
    (comp (ref "R2")
      (value "4K7")
      (footprint "R0402 Reflow")
      (description "RES SMD 4.7K OHM 1% 1/16W 0402")
      (fields
        (field (name "TOLERANCE") "±1%")
        (field (name "02. DISTRIBUTOR PART NUMBER") "311-4.7KLRDKR-ND")
        (field (name "13. CREATED DATE/NAME") "AUG2018/Hören")
      )
      (libsource (lib "chickenfood") (part "R"))
    )
    (comp (ref "R3")
      (value "4K7")
      (footprint "R0402 Reflow")
      (description "RES SMD 4.7K OHM 1% 1/16W 0402")
      (fields
        (field (name "TOLERANCE") "±1%")
        (field (name "02. DISTRIBUTOR PART NUMBER") "311-4.7KLRDKR-ND")
        (field (name "13. CREATED DATE/NAME") "AUG2018/Hören")
      )
      (libsource (lib "chickenfood") (part "R"))
    )
    (comp (ref "R4")
      (value "4K7")
      (footprint "R0402 Reflow")
      (description "RES SMD 4.7K OHM 1% 1/16W 0402")
      (fields
        (field (name "TOLERANCE") "±1%")
        (field (name "02. DISTRIBUTOR PART NUMBER") "311-4.7KLRDKR-ND")
        (field (name "13. CREATED DATE/NAME") "AUG2018/Hören")
      )
      (libsource (lib "chickenfood") (part "R"))
    )
    (comp (ref "R5")
      (value "4K7")
      (footprint "R0402 Reflow")
      (description "RES SMD 4.7K OHM 1% 1/16W 0402")
      (fields
        (field (name "TOLERANCE") "±1%")
        (field (name "02. DISTRIBUTOR PART NUMBER") "311-4.7KLRDKR-ND")
        (field (name "13. CREATED DATE/NAME") "AUG2018/Hören")
      )
      (libsource (lib "chickenfood") (part "R"))
    )
    (comp (ref "R6")
      (value "4K7")
      (footprint "R0402 Reflow")
      (description "RES SMD 4.7K OHM 1% 1/16W 0402")
      (fields
        (field (name "TOLERANCE") "±1%")
        (field (name "02. DISTRIBUTOR PART NUMBER") "311-4.7KLRDKR-ND")
        (field (name "13. CREATED DATE/NAME") "AUG2018/Hören")
      )
      (libsource (lib "chickenfood") (part "R"))
    )
    (comp (ref "R7")
      (value "4K7")
      (footprint "R0402 Reflow")
      (description "RES SMD 4.7K OHM 1% 1/16W 0402")
      (fields
        (field (name "TOLERANCE") "±1%")
        (field (name "02. DISTRIBUTOR PART NUMBER") "311-4.7KLRDKR-ND")
        (field (name "13. CREATED DATE/NAME") "AUG2018/Hören")
      )
      (libsource (lib "chickenfood") (part "R"))
    )
    (comp (ref "R8")
      (value "4K7")
      (footprint "R0402 Reflow")
      (description "RES SMD 4.7K OHM 1% 1/16W 0402")
      (fields
        (field (name "TOLERANCE") "±1%")
        (field (name "02. DISTRIBUTOR PART NUMBER") "311-4.7KLRDKR-ND")
        (field (name "13. CREATED DATE/NAME") "AUG2018/Hören")
      )
      (libsource (lib "chickenfood") (part "R"))
    )
    (comp (ref "R9")
      (value "4K7")
      (footprint "R0402 Reflow")
      (description "RES SMD 4.7K OHM 1% 1/16W 0402")
      (fields
        (field (name "TOLERANCE") "±1%")
        (field (name "02. DISTRIBUTOR PART NUMBER") "311-4.7KLRDKR-ND")
        (field (name "13. CREATED DATE/NAME") "AUG2018/Hören")
      )
      (libsource (lib "chickenfood") (part "R"))
    )
    (comp (ref "R10")
      (value "4K7")
      (footprint "R0402 Reflow")
      (description "RES SMD 4.7K OHM 1% 1/16W 0402")
      (fields
        (field (name "TOLERANCE") "±1%")
        (field (name "02. DISTRIBUTOR PART NUMBER") "311-4.7KLRDKR-ND")
        (field (name "13. CREATED DATE/NAME") "AUG2018/Hören")
      )
      (libsource (lib "chickenfood") (part "R"))
    )
    (comp (ref "R11")
      (value "4K7")
      (footprint "R0402 Reflow")
      (description "RES SMD 4.7K OHM 1% 1/16W 0402")
      (fields
        (field (name "TOLERANCE") "±1%")
        (field (name "02. DISTRIBUTOR PART NUMBER") "311-4.7KLRDKR-ND")
        (field (name "13. CREATED DATE/NAME") "AUG2018/Hören")
      )
      (libsource (lib "chickenfood") (part "R"))
    )
    (comp (ref "R12")
      (value "4K7")
      (footprint "R0402 Reflow")
      (description "RES SMD 4.7K OHM 1% 1/16W 0402")
      (fields
        (field (name "TOLERANCE") "±1%")
        (field (name "02. DISTRIBUTOR PART NUMBER") "311-4.7KLRDKR-ND")
        (field (name "13. CREATED DATE/NAME") "AUG2018/Hören")
      )
      (libsource (lib "chickenfood") (part "R"))
    )
    (comp (ref "R13")
      (value "4K7")
      (footprint "R0402 Reflow")
      (description "RES SMD 4.7K OHM 1% 1/16W 0402")
      (fields
        (field (name "TOLERANCE") "±1%")
        (field (name "02. DISTRIBUTOR PART NUMBER") "311-4.7KLRDKR-ND")
        (field (name "13. CREATED DATE/NAME") "AUG2018/Hören")
      )
      (libsource (lib "chickenfood") (part "R"))
    )
    (comp (ref "R14")
      (value "4K7")
      (footprint "R0402 Reflow")
      (description "RES SMD 4.7K OHM 1% 1/16W 0402")
      (fields
        (field (name "TOLERANCE") "±1%")
        (field (name "02. DISTRIBUTOR PART NUMBER") "311-4.7KLRDKR-ND")
        (field (name "13. CREATED DATE/NAME") "AUG2018/Hören")
      )
      (libsource (lib "chickenfood") (part "R"))
    )
    (comp (ref "R15")
      (value "4K7")
      (footprint "R0402 Reflow")
      (description "RES SMD 4.7K OHM 1% 1/16W 0402")
      (fields
        (field (name "TOLERANCE") "±1%")
        (field (name "02. DISTRIBUTOR PART NUMBER") "311-4.7KLRDKR-ND")
        (field (name "13. CREATED DATE/NAME") "AUG2018/Hören")
      )
      (libsource (lib "chickenfood") (part "R"))
    )
    (comp (ref "R16")
      (value "4K7")
      (footprint "R0402 Reflow")
      (description "RES SMD 4.7K OHM 1% 1/16W 0402")
      (fields
        (field (name "TOLERANCE") "±1%")
        (field (name "02. DISTRIBUTOR PART NUMBER") "311-4.7KLRDKR-ND")
        (field (name "13. CREATED DATE/NAME") "AUG2018/Hören")
      )
      (libsource (lib "chickenfood") (part "R"))
    )
    (comp (ref "R17")
      (value "4K7")
      (footprint "R0402 Reflow")
      (description "RES SMD 4.7K OHM 1% 1/16W 0402")
      (fields
        (field (name "TOLERANCE") "±1%")
        (field (name "02. DISTRIBUTOR PART NUMBER") "311-4.7KLRDKR-ND")
        (field (name "13. CREATED DATE/NAME") "AUG2018/Hören")
      )
      (libsource (lib "chickenfood") (part "R"))
    )
    (comp (ref "R18")
      (value "4K7")
      (footprint "R0402 Reflow")
      (description "RES SMD 4.7K OHM 1% 1/16W 0402")
      (fields
        (field (name "TOLERANCE") "±1%")
        (field (name "02. DISTRIBUTOR PART NUMBER") "311-4.7KLRDKR-ND")
        (field (name "13. CREATED DATE/NAME") "AUG2018/Hören")
      )
      (libsource (lib "chickenfood") (part "R"))
    )
    (comp (ref "R19")
      (value "4K7")
      (footprint "R0402 Reflow")
      (description "RES SMD 4.7K OHM 1% 1/16W 0402")
      (fields
        (field (name "TOLERANCE") "±1%")
        (field (name "02. DISTRIBUTOR PART NUMBER") "311-4.7KLRDKR-ND")
        (field (name "13. CREATED DATE/NAME") "AUG2018/Hören")
      )
      (libsource (lib "chickenfood") (part "R"))
    )
    (comp (ref "R20")
      (value "4K7")
      (footprint "R0402 Reflow")
      (description "RES SMD 4.7K OHM 1% 1/16W 0402")
      (fields
        (field (name "TOLERANCE") "±1%")
        (field (name "02. DISTRIBUTOR PART NUMBER") "311-4.7KLRDKR-ND")
        (field (name "13. CREATED DATE/NAME") "AUG2018/Hören")
      )
      (libsource (lib "chickenfood") (part "R"))
    )
    (comp (ref "R21")
      (value "4K7")
      (footprint "R0402 Reflow")
      (description "RES SMD 4.7K OHM 1% 1/16W 0402")
      (fields
        (field (name "TOLERANCE") "±1%")
        (field (name "02. DISTRIBUTOR PART NUMBER") "311-4.7KLRDKR-ND")
        (field (name "13. CREATED DATE/NAME") "AUG2018/Hören")
      )
      (libsource (lib "chickenfood") (part "R"))
    )
    (comp (ref "R22")
      (value "4K7")
      (footprint "R0402 Reflow")
      (description "RES SMD 4.7K OHM 1% 1/16W 0402")
      (fields
        (field (name "TOLERANCE") "±1%")
        (field (name "02. DISTRIBUTOR PART NUMBER") "311-4.7KLRDKR-ND")
        (field (name "13. CREATED DATE/NAME") "AUG2018/Hören")
      )
      (libsource (lib "chickenfood") (part "R"))
    )
    (comp (ref "R23")
      (value "4K7")
      (footprint "R0402 Reflow")
      (description "RES SMD 4.7K OHM 1% 1/16W 0402")
      (fields
        (field (name "TOLERANCE") "±1%")
        (field (name "02. DISTRIBUTOR PART NUMBER") "311-4.7KLRDKR-ND")
        (field (name "13. CREATED DATE/NAME") "AUG2018/Hören")
      )
      (libsource (lib "chickenfood") (part "R"))
    )
    (comp (ref "R24")
      (value "4K7")
      (footprint "R0402 Reflow")
      (description "RES SMD 4.7K OHM 1% 1/16W 0402")
      (fields
        (field (name "TOLERANCE") "±1%")
        (field (name "02. DISTRIBUTOR PART NUMBER") "311-4.7KLRDKR-ND")
        (field (name "13. CREATED DATE/NAME") "AUG2018/Hören")
      )
      (libsource (lib "chickenfood") (part "R"))
    )
    (comp (ref "R25")
      (value "4K7")
      (footprint "R0402 Reflow")
      (description "RES SMD 4.7K OHM 1% 1/16W 0402")
      (fields
        (field (name "TOLERANCE") "±1%")
        (field (name "02. DISTRIBUTOR PART NUMBER") "311-4.7KLRDKR-ND")
        (field (name "13. CREATED DATE/NAME") "AUG2018/Hören")
      )
      (libsource (lib "chickenfood") (part "R"))
    )
    (comp (ref "R26")
      (value "4K7")
      (footprint "R0402 Reflow")
      (description "RES SMD 4.7K OHM 1% 1/16W 0402")
      (fields
        (field (name "TOLERANCE") "±1%")
        (field (name "02. DISTRIBUTOR PART NUMBER") "311-4.7KLRDKR-ND")
        (field (name "13. CREATED DATE/NAME") "AUG2018/Hören")
      )
      (libsource (lib "chickenfood") (part "R"))
    )
    (comp (ref "R27")
      (value "4K7")
      (footprint "R0402 Reflow")
      (description "RES SMD 4.7K OHM 1% 1/16W 0402")
      (fields
        (field (name "TOLERANCE") "±1%")
        (field (name "02. DISTRIBUTOR PART NUMBER") "311-4.7KLRDKR-ND")
        (field (name "13. CREATED DATE/NAME") "AUG2018/Hören")
      )
      (libsource (lib "chickenfood") (part "R"))
    )
    (comp (ref "R28")
      (value "4K7")
      (footprint "R0402 Reflow")
      (description "RES SMD 4.7K OHM 1% 1/16W 0402")
      (fields
        (field (name "TOLERANCE") "±1%")
        (field (name "02. DISTRIBUTOR PART NUMBER") "311-4.7KLRDKR-ND")
        (field (name "13. CREATED DATE/NAME") "AUG2018/Hören")
      )
      (libsource (lib "chickenfood") (part "R"))
    )
    (comp (ref "R29")
      (value "4K7")
      (footprint "R0402 Reflow")
      (description "RES SMD 4.7K OHM 1% 1/16W 0402")
      (fields
        (field (name "TOLERANCE") "±1%")
        (field (name "02. DISTRIBUTOR PART NUMBER") "311-4.7KLRDKR-ND")
        (field (name "13. CREATED DATE/NAME") "AUG2018/Hören")
      )
      (libsource (lib "chickenfood") (part "R"))
    )
    (comp (ref "R30")
      (value "4K7")
      (footprint "R0402 Reflow")
      (description "RES SMD 4.7K OHM 1% 1/16W 0402")
      (fields
        (field (name "TOLERANCE") "±1%")
        (field (name "02. DISTRIBUTOR PART NUMBER") "311-4.7KLRDKR-ND")
        (field (name "13. CREATED DATE/NAME") "AUG2018/Hören")
      )
      (libsource (lib "chickenfood") (part "R"))
    )
    (comp (ref "R31")
      (value "4K7")
      (footprint "R0402 Reflow")
      (description "RES SMD 4.7K OHM 1% 1/16W 0402")
      (fields
        (field (name "TOLERANCE") "±1%")
        (field (name "02. DISTRIBUTOR PART NUMBER") "311-4.7KLRDKR-ND")
        (field (name "13. CREATED DATE/NAME") "AUG2018/Hören")
      )
      (libsource (lib "chickenfood") (part "R"))
    )
    (comp (ref "R32")
      (value "4K7")
      (footprint "R0402 Reflow")
      (description "RES SMD 4.7K OHM 1% 1/16W 0402")
      (fields
        (field (name "TOLERANCE") "±1%")
        (field (name "02. DISTRIBUTOR PART NUMBER") "311-4.7KLRDKR-ND")
        (field (name "13. CREATED DATE/NAME") "AUG2018/Hören")
      )
      (libsource (lib "chickenfood") (part "R"))
    )
    (comp (ref "R33")
      (value "4K7")
      (footprint "R0402 Reflow")
      (description "RES SMD 4.7K OHM 1% 1/16W 0402")
      (fields
        (field (name "TOLERANCE") "±1%")
        (field (name "02. DISTRIBUTOR PART NUMBER") "311-4.7KLRDKR-ND")
        (field (name "13. CREATED DATE/NAME") "AUG2018/Hören")
      )
      (libsource (lib "chickenfood") (part "R"))
    )
    (comp (ref "R34")
      (value "4K7")
      (footprint "R0402 Reflow")
      (description "RES SMD 4.7K OHM 1% 1/16W 0402")
      (fields
        (field (name "TOLERANCE") "±1%")
        (field (name "02. DISTRIBUTOR PART NUMBER") "311-4.7KLRDKR-ND")
        (field (name "13. CREATED DATE/NAME") "AUG2018/Hören")
      )
      (libsource (lib "chickenfood") (part "R"))
    )
    (comp (ref "R35")
      (value "4K7")
      (footprint "R0402 Reflow")
      (description "RES SMD 4.7K OHM 1% 1/16W 0402")
      (fields
        (field (name "TOLERANCE") "±1%")
        (field (name "02. DISTRIBUTOR PART NUMBER") "311-4.7KLRDKR-ND")
        (field (name "13. CREATED DATE/NAME") "AUG2018/Hören")
      )
      (libsource (lib "chickenfood") (part "R"))
    )
    (comp (ref "R36")
      (value "4K7")
      (footprint "R0402 Reflow")
      (description "RES SMD 4.7K OHM 1% 1/16W 0402")
      (fields
        (field (name "TOLERANCE") "±1%")
        (field (name "02. DISTRIBUTOR PART NUMBER") "311-4.7KLRDKR-ND")
        (field (name "13. CREATED DATE/NAME") "AUG2018/Hören")
      )
      (libsource (lib "chickenfood") (part "R"))
    )
    (comp (ref "R37")
      (value "4K7")
      (footprint "R0402 Reflow")
      (description "RES SMD 4.7K OHM 1% 1/16W 0402")
      (fields
        (field (name "TOLERANCE") "±1%")
        (field (name "02. DISTRIBUTOR PART NUMBER") "311-4.7KLRDKR-ND")
        (field (name "13. CREATED DATE/NAME") "AUG2018/Hören")
      )
      (libsource (lib "chickenfood") (part "R"))
    )
    (comp (ref "R38")
      (value "4K7")
      (footprint "R0402 Reflow")
      (description "RES SMD 4.7K OHM 1% 1/16W 0402")
      (fields
        (field (name "TOLERANCE") "±1%")
        (field (name "02. DISTRIBUTOR PART NUMBER") "311-4.7KLRDKR-ND")
        (field (name "13. CREATED DATE/NAME") "AUG2018/Hören")
      )
      (libsource (lib "chickenfood") (part "R"))
    )
    (comp (ref "R39")
      (value "4K7")
      (footprint "R0402 Reflow")
      (description "RES SMD 4.7K OHM 1% 1/16W 0402")
      (fields
        (field (name "TOLERANCE") "±1%")
        (field (name "02. DISTRIBUTOR PART NUMBER") "311-4.7KLRDKR-ND")
        (field (name "13. CREATED DATE/NAME") "AUG2018/Hören")
      )
      (libsource (lib "chickenfood") (part "R"))
    )
    (comp (ref "R40")
      (value "4K7")
      (footprint "R0402 Reflow")
      (description "RES SMD 4.7K OHM 1% 1/16W 0402")
      (fields
        (field (name "TOLERANCE") "±1%")
        (field (name "02. DISTRIBUTOR PART NUMBER") "311-4.7KLRDKR-ND")
        (field (name "13. CREATED DATE/NAME") "AUG2018/Hören")
      )
      (libsource (lib "chickenfood") (part "R"))
    )
    (comp (ref "R41")
      (value "4K7")
      (footprint "R0402 Reflow")
      (description "RES SMD 4.7K OHM 1% 1/16W 0402")
      (fields
        (field (name "TOLERANCE") "±1%")
        (field (name "02. DISTRIBUTOR PART NUMBER") "311-4.7KLRDKR-ND")
        (field (name "13. CREATED DATE/NAME") "AUG2018/Hören")
      )
      (libsource (lib "chickenfood") (part "R"))
    )
    (comp (ref "R42")
      (value "4K7")
      (footprint "R0402 Reflow")
      (description "RES SMD 4.7K OHM 1% 1/16W 0402")
      (fields
        (field (name "TOLERANCE") "±1%")
        (field (name "02. DISTRIBUTOR PART NUMBER") "311-4.7KLRDKR-ND")
        (field (name "13. CREATED DATE/NAME") "AUG2018/Hören")
      )
      (libsource (lib "chickenfood") (part "R"))
    )
    (comp (ref "R48")
      (value "4K7")
      (footprint "R0402 Reflow")
      (description "RES SMD 4.7K OHM 1% 1/16W 0402")
      (fields
        (field (name "TOLERANCE") "±1%")
        (field (name "02. DISTRIBUTOR PART NUMBER") "311-4.7KLRDKR-ND")
        (field (name "13. CREATED DATE/NAME") "AUG2018/Hören")
      )
      (libsource (lib "chickenfood") (part "R"))
    )
    (comp (ref "R49")
      (value "4K7")
      (footprint "R0402 Reflow")
      (description "RES SMD 4.7K OHM 1% 1/16W 0402")
      (fields
        (field (name "TOLERANCE") "±1%")
        (field (name "02. DISTRIBUTOR PART NUMBER") "311-4.7KLRDKR-ND")
        (field (name "13. CREATED DATE/NAME") "AUG2018/Hören")
      )
      (libsource (lib "chickenfood") (part "R"))
    )
    (comp (ref "R50")
      (value "4K7")
      (footprint "R0402 Reflow")
      (description "RES SMD 4.7K OHM 1% 1/16W 0402")
      (fields
        (field (name "TOLERANCE") "±1%")
        (field (name "02. DISTRIBUTOR PART NUMBER") "311-4.7KLRDKR-ND")
        (field (name "13. CREATED DATE/NAME") "AUG2018/Hören")
      )
      (libsource (lib "chickenfood") (part "R"))
    )
    (comp (ref "R51")
      (value "4K7")
      (footprint "R0402 Reflow")
      (description "RES SMD 4.7K OHM 1% 1/16W 0402")
      (fields
        (field (name "TOLERANCE") "±1%")
        (field (name "02. DISTRIBUTOR PART NUMBER") "311-4.7KLRDKR-ND")
        (field (name "13. CREATED DATE/NAME") "AUG2018/Hören")
      )
      (libsource (lib "chickenfood") (part "R"))
    )
    (comp (ref "R52")
      (value "4K7")
      (footprint "R0402 Reflow")
      (description "RES SMD 4.7K OHM 1% 1/16W 0402")
      (fields
        (field (name "TOLERANCE") "±1%")
        (field (name "02. DISTRIBUTOR PART NUMBER") "311-4.7KLRDKR-ND")
        (field (name "13. CREATED DATE/NAME") "AUG2018/Hören")
      )
      (libsource (lib "chickenfood") (part "R"))
    )
    (comp (ref "R53")
      (value "4K7")
      (footprint "R0402 Reflow")
      (description "RES SMD 4.7K OHM 1% 1/16W 0402")
      (fields
        (field (name "TOLERANCE") "±1%")
        (field (name "02. DISTRIBUTOR PART NUMBER") "311-4.7KLRDKR-ND")
        (field (name "13. CREATED DATE/NAME") "AUG2018/Hören")
      )
      (libsource (lib "chickenfood") (part "R"))
    )
    (comp (ref "R54")
      (value "4K7")
      (footprint "R0402 Reflow")
      (description "RES SMD 4.7K OHM 1% 1/16W 0402")
      (fields
        (field (name "TOLERANCE") "±1%")
        (field (name "02. DISTRIBUTOR PART NUMBER") "311-4.7KLRDKR-ND")
        (field (name "13. CREATED DATE/NAME") "AUG2018/Hören")
      )
      (libsource (lib "chickenfood") (part "R"))
    )
    (comp (ref "R55")
      (value "4K7")
      (footprint "R0402 Reflow")
      (description "RES SMD 4.7K OHM 1% 1/16W 0402")
      (fields
        (field (name "TOLERANCE") "±1%")
        (field (name "02. DISTRIBUTOR PART NUMBER") "311-4.7KLRDKR-ND")
        (field (name "13. CREATED DATE/NAME") "AUG2018/Hören")
      )
      (libsource (lib "chickenfood") (part "R"))
    )
    (comp (ref "R56")
      (value "4K7")
      (footprint "R0402 Reflow")
      (description "RES SMD 4.7K OHM 1% 1/16W 0402")
      (fields
        (field (name "TOLERANCE") "±1%")
        (field (name "02. DISTRIBUTOR PART NUMBER") "311-4.7KLRDKR-ND")
        (field (name "13. CREATED DATE/NAME") "AUG2018/Hören")
      )
      (libsource (lib "chickenfood") (part "R"))
    )
    (comp (ref "R57")
      (value "4K7")
      (footprint "R0402 Reflow")
      (description "RES SMD 4.7K OHM 1% 1/16W 0402")
      (fields
        (field (name "TOLERANCE") "±1%")
        (field (name "02. DISTRIBUTOR PART NUMBER") "311-4.7KLRDKR-ND")
        (field (name "13. CREATED DATE/NAME") "AUG2018/Hören")
      )
      (libsource (lib "chickenfood") (part "R"))
    )
    (comp (ref "R58")
      (value "4K7")
      (footprint "R0402 Reflow")
      (description "RES SMD 4.7K OHM 1% 1/16W 0402")
      (fields
        (field (name "TOLERANCE") "±1%")
        (field (name "02. DISTRIBUTOR PART NUMBER") "311-4.7KLRDKR-ND")
        (field (name "13. CREATED DATE/NAME") "AUG2018/Hören")
      )
      (libsource (lib "chickenfood") (part "R"))
    )
    (comp (ref "R59")
      (value "4K7")
      (footprint "R0402 Reflow")
      (description "RES SMD 4.7K OHM 1% 1/16W 0402")
      (fields
        (field (name "TOLERANCE") "±1%")
        (field (name "02. DISTRIBUTOR PART NUMBER") "311-4.7KLRDKR-ND")
        (field (name "13. CREATED DATE/NAME") "AUG2018/Hören")
      )
      (libsource (lib "chickenfood") (part "R"))
    )
    (comp (ref "R60")
      (value "4K7")
      (footprint "R0402 Reflow")
      (description "RES SMD 4.7K OHM 1% 1/16W 0402")
      (fields
        (field (name "TOLERANCE") "±1%")
        (field (name "02. DISTRIBUTOR PART NUMBER") "311-4.7KLRDKR-ND")
        (field (name "13. CREATED DATE/NAME") "AUG2018/Hören")
      )
      (libsource (lib "chickenfood") (part "R"))
    )
    (comp (ref "R61")
      (value "4K7")
      (footprint "R0402 Reflow")
      (description "RES SMD 4.7K OHM 1% 1/16W 0402")
      (fields
        (field (name "TOLERANCE") "±1%")
        (field (name "02. DISTRIBUTOR PART NUMBER") "311-4.7KLRDKR-ND")
        (field (name "13. CREATED DATE/NAME") "AUG2018/Hören")
      )
      (libsource (lib "chickenfood") (part "R"))
    )
    (comp (ref "R62")
      (value "4K7")
      (footprint "R0402 Reflow")
      (description "RES SMD 4.7K OHM 1% 1/16W 0402")
      (fields
        (field (name "TOLERANCE") "±1%")
        (field (name "02. DISTRIBUTOR PART NUMBER") "311-4.7KLRDKR-ND")
        (field (name "13. CREATED DATE/NAME") "AUG2018/Hören")
      )
      (libsource (lib "chickenfood") (part "R"))
    )
    (comp (ref "R63")
      (value "4K7")
      (footprint "R0402 Reflow")
      (description "RES SMD 4.7K OHM 1% 1/16W 0402")
      (fields
        (field (name "TOLERANCE") "±1%")
        (field (name "02. DISTRIBUTOR PART NUMBER") "311-4.7KLRDKR-ND")
        (field (name "13. CREATED DATE/NAME") "AUG2018/Hören")
      )
      (libsource (lib "chickenfood") (part "R"))
    )
    (comp (ref "R64")
      (value "4K7")
      (footprint "R0402 Reflow")
      (description "RES SMD 4.7K OHM 1% 1/16W 0402")
      (fields
        (field (name "TOLERANCE") "±1%")
        (field (name "02. DISTRIBUTOR PART NUMBER") "311-4.7KLRDKR-ND")
        (field (name "13. CREATED DATE/NAME") "AUG2018/Hören")
      )
      (libsource (lib "chickenfood") (part "R"))
    )
    (comp (ref "R65")
      (value "4K7")
      (footprint "R0402 Reflow")
      (description "RES SMD 4.7K OHM 1% 1/16W 0402")
      (fields
        (field (name "TOLERANCE") "±1%")
        (field (name "02. DISTRIBUTOR PART NUMBER") "311-4.7KLRDKR-ND")
        (field (name "13. CREATED DATE/NAME") "AUG2018/Hören")
      )
      (libsource (lib "chickenfood") (part "R"))
    )
    (comp (ref "R66")
      (value "4K7")
      (footprint "R0402 Reflow")
      (description "RES SMD 4.7K OHM 1% 1/16W 0402")
      (fields
        (field (name "TOLERANCE") "±1%")
        (field (name "02. DISTRIBUTOR PART NUMBER") "311-4.7KLRDKR-ND")
        (field (name "13. CREATED DATE/NAME") "AUG2018/Hören")
      )
      (libsource (lib "chickenfood") (part "R"))
    )
    (comp (ref "R67")
      (value "4K7")
      (footprint "R0402 Reflow")
      (description "RES SMD 4.7K OHM 1% 1/16W 0402")
      (fields
        (field (name "TOLERANCE") "±1%")
        (field (name "02. DISTRIBUTOR PART NUMBER") "311-4.7KLRDKR-ND")
        (field (name "13. CREATED DATE/NAME") "AUG2018/Hören")
      )
      (libsource (lib "chickenfood") (part "R"))
    )
    (comp (ref "R68")
      (value "4K7")
      (footprint "R0402 Reflow")
      (description "RES SMD 4.7K OHM 1% 1/16W 0402")
      (fields
        (field (name "TOLERANCE") "±1%")
        (field (name "02. DISTRIBUTOR PART NUMBER") "311-4.7KLRDKR-ND")
        (field (name "13. CREATED DATE/NAME") "AUG2018/Hören")
      )
      (libsource (lib "chickenfood") (part "R"))
    )
    (comp (ref "R69")
      (value "4K7")
      (footprint "R0402 Reflow")
      (description "RES SMD 4.7K OHM 1% 1/16W 0402")
      (fields
        (field (name "TOLERANCE") "±1%")
        (field (name "02. DISTRIBUTOR PART NUMBER") "311-4.7KLRDKR-ND")
        (field (name "13. CREATED DATE/NAME") "AUG2018/Hören")
      )
      (libsource (lib "chickenfood") (part "R"))
    )
    (comp (ref "R121")
      (value "10k")
      (footprint "R0402 Reflow")
      (description "RES SMD 10K OHM 1% 1/16W 0402")
      (fields
        (field (name "TOLERANCE") "±1%")
        (field (name "02. DISTRIBUTOR PART NUMBER") "311-10.0KLRDKR-ND")
        (field (name "13. CREATED DATE/NAME") "AUG2018/Hören")
      )
      (libsource (lib "chickenfood") (part "R"))
    )
    (comp (ref "R125")
      (value "3k6")
      (footprint "R0603 Reflow")
      (description "RES SMD 3.6K OHM 1% 1/10W 0603")
      (fields
        (field (name "TOLERANCE") "±1%")
        (field (name "02. DISTRIBUTOR PART NUMBER") "311-3.60KHRCT-ND")
        (field (name "13. CREATED DATE/NAME") "AUG2018/Hören")
      )
      (libsource (lib "chickenfood") (part "R"))
    )
    (comp (ref "R130")
      (value "4K7")
      (footprint "R0402 Reflow")
      (description "RES SMD 4.7K OHM 1% 1/16W 0402")
      (fields
        (field (name "TOLERANCE") "±1%")
        (field (name "02. DISTRIBUTOR PART NUMBER") "311-4.7KLRDKR-ND")
        (field (name "13. CREATED DATE/NAME") "AUG2018/Hören")
      )
      (libsource (lib "chickenfood") (part "R"))
    )
    (comp (ref "TP5")
      (value "TP")
      (footprint "DualTestpoint 100mils")
      (description "Dual testpoint, pitch 2.54mm")
      (fields
        (field (name "02. DISTRIBUTOR PART NUMBER") "HMTSW-103-07-G-S-240")
        (field (name "13. CREATED DATE/NAME") "AUG2018/Hören")
      )
      (libsource (lib "PCB-Tester-Board-V1") (part "DualTestpoint 100mils"))
    )
    (comp (ref "TP6")
      (value "TP")
      (footprint "DualTestpoint 100mils")
      (description "Dual testpoint, pitch 2.54mm")
      (fields
        (field (name "02. DISTRIBUTOR PART NUMBER") "HMTSW-103-07-G-S-240")
        (field (name "13. CREATED DATE/NAME") "AUG2018/Hören")
      )
      (libsource (lib "PCB-Tester-Board-V1") (part "DualTestpoint 100mils"))
    )
    (comp (ref "X1")
      (value "X")
      (description "32 x 2 x 1.27mm SOCKET DISCRETE CABL COLORED")
      (fields
        (field (name "02. DISTRIBUTOR PART NUMBER") "SFSD-32-30C-G-15.00-S")
        (field (name "13. CREATED DATE/NAME") "??? / Hören")
      )
      (libsource (lib "PCB-Relay-Board-V1") (part "SFSD-32-30C-G-15.00-S"))
    )
    (comp (ref "X2")
      (value "X")
      (footprint "TFC-132-01-F-D-RA")
      (description "CONN HEADER TH RA 48POS 1.27MM")
      (fields
        (field (name "02. DISTRIBUTOR PART NUMBER") "TFC-132-01-F-D-RA")
        (field (name "13. CREATED DATE/NAME") "??? / Hören")
      )
      (libsource (lib "PCB-Relay-Board-V1") (part "TFC-132-01-F-D-RA"))
    )
    (comp (ref "X3")
      (value "X")
      (footprint "CONFIG64")
      (description "PCB Tester Configuration Matrix for 48 Relays over 8 ABUSes")
      (fields (field (name "13. CREATED DATE/NAME") "??? / Hören"))
      (libsource (lib "PCB-Relay-Board-V1") (part "CONFIG64"))
    )
    (comp (ref "X4")
      (value "X")
      (footprint "PCIE-036-02-F-D-Fingers")
      (description "CONN PCI Card Edge 36POS")
      (libsource (lib "Connectors") (part "PCIE-036-02-F-D-Fingers"))
    )
  )
  (nets
    (net (code "4") (name "/A0") (class "Default")
      (node (ref "X4") (pin "B18") (pinfunction "B18_B18") (pintype "passive"))
    )
    (net (code "5") (name "/A1") (class "Default")
      (node (ref "X4") (pin "A18") (pinfunction "A18_A18") (pintype "passive"))
    )
    (net (code "6") (name "/A2") (class "Default")
      (node (ref "X4") (pin "B17") (pinfunction "B17_B17") (pintype "passive"))
    )
    (net (code "7") (name "/A3") (class "Default")
      (node (ref "X4") (pin "A17") (pinfunction "A17_A17") (pintype "passive"))
    )
    (net (code "8") (name "/ABUS0") (class "Default")
      (node (ref "X3") (pin "ABUS0") (pinfunction "ABUS0_ABUS0") (pintype "passive"))
      (node (ref "X4") (pin "A5") (pinfunction "A5_A5") (pintype "passive"))
    )
    (net (code "9") (name "/ABUS1") (class "Default")
      (node (ref "X3") (pin "ABUS1") (pinfunction "ABUS1_ABUS1") (pintype "passive"))
      (node (ref "X4") (pin "B5") (pinfunction "B5_B5") (pintype "passive"))
    )
    (net (code "10") (name "/ABUS2") (class "Default")
      (node (ref "X3") (pin "ABUS2") (pinfunction "ABUS2_ABUS2") (pintype "passive"))
      (node (ref "X4") (pin "A4") (pinfunction "A4_A4") (pintype "passive"))
    )
    (net (code "11") (name "/ABUS3") (class "Default")
      (node (ref "X3") (pin "ABUS3") (pinfunction "ABUS3_ABUS3") (pintype "passive"))
      (node (ref "X4") (pin "B4") (pinfunction "B4_B4") (pintype "passive"))
    )
    (net (code "12") (name "/ABUS4") (class "Default")
      (node (ref "X3") (pin "ABUS4") (pinfunction "ABUS4_ABUS4") (pintype "passive"))
      (node (ref "X4") (pin "A3") (pinfunction "A3_A3") (pintype "passive"))
    )
    (net (code "13") (name "/ABUS5") (class "Default")
      (node (ref "X3") (pin "ABUS5") (pinfunction "ABUS5_ABUS5") (pintype "passive"))
      (node (ref "X4") (pin "B3") (pinfunction "B3_B3") (pintype "passive"))
    )
    (net (code "14") (name "/ABUS6") (class "Default")
      (node (ref "X3") (pin "ABUS6") (pinfunction "ABUS6_ABUS6") (pintype "passive"))
      (node (ref "X4") (pin "A2") (pinfunction "A2_A2") (pintype "passive"))
    )
    (net (code "15") (name "/ABUS7") (class "Default")
      (node (ref "X3") (pin "ABUS7") (pinfunction "ABUS7_ABUS7") (pintype "passive"))
      (node (ref "X4") (pin "B2") (pinfunction "B2_B2") (pintype "passive"))
    )
    (net (code "17") (name "/ALERT#") (class "Default")
      (node (ref "J11") (pin "5") (pinfunction "5_5") (pintype "passive"))
    )
    (net (code "18") (name "/CLK") (class "Default")
      (node (ref "J11") (pin "7") (pinfunction "7_7") (pintype "passive"))
    )
    (net (code "19") (name "/CS") (class "Default")
      (node (ref "R121") (pin "1") (pinfunction "1_1") (pintype "passive"))
      (node (ref "X4") (pin "B15") (pinfunction "B15_B15") (pintype "passive"))
    )
    (net (code "20") (name "/DATA") (class "Default")
      (node (ref "J11") (pin "9") (pinfunction "9_9") (pintype "passive"))
    )
    (net (code "21") (name "/DRV1") (class "Default")
      (node (ref "Q1") (pin "1") (pinfunction "G_1") (pintype "passive"))
      (node (ref "R1") (pin "2") (pinfunction "2_2") (pintype "passive"))
    )
    (net (code "22") (name "/DRV2") (class "Default")
      (node (ref "Q2") (pin "1") (pinfunction "G_1") (pintype "passive"))
      (node (ref "R2") (pin "2") (pinfunction "2_2") (pintype "passive"))
    )
    (net (code "23") (name "/DRV3") (class "Default")
      (node (ref "Q3") (pin "1") (pinfunction "G_1") (pintype "passive"))
      (node (ref "R3") (pin "2") (pinfunction "2_2") (pintype "passive"))
    )
    (net (code "24") (name "/DRV4") (class "Default")
      (node (ref "Q4") (pin "1") (pinfunction "G_1") (pintype "passive"))
      (node (ref "R4") (pin "2") (pinfunction "2_2") (pintype "passive"))
    )
    (net (code "25") (name "/DRV5") (class "Default")
      (node (ref "Q5") (pin "1") (pinfunction "G_1") (pintype "passive"))
      (node (ref "R5") (pin "2") (pinfunction "2_2") (pintype "passive"))
    )
    (net (code "26") (name "/DRV6") (class "Default")
      (node (ref "Q6") (pin "1") (pinfunction "G_1") (pintype "passive"))
      (node (ref "R6") (pin "2") (pinfunction "2_2") (pintype "passive"))
    )
    (net (code "27") (name "/DRV7") (class "Default")
      (node (ref "Q7") (pin "1") (pinfunction "G_1") (pintype "passive"))
      (node (ref "R7") (pin "2") (pinfunction "2_2") (pintype "passive"))
    )
    (net (code "28") (name "/DRV8") (class "Default")
      (node (ref "Q8") (pin "1") (pinfunction "G_1") (pintype "passive"))
      (node (ref "R8") (pin "2") (pinfunction "2_2") (pintype "passive"))
    )
    (net (code "29") (name "/DRV9") (class "Default")
      (node (ref "Q9") (pin "1") (pinfunction "G_1") (pintype "passive"))
      (node (ref "R9") (pin "2") (pinfunction "2_2") (pintype "passive"))
    )
    (net (code "30") (name "/DRV10") (class "Default")
      (node (ref "Q10") (pin "1") (pinfunction "G_1") (pintype "passive"))
      (node (ref "R10") (pin "2") (pinfunction "2_2") (pintype "passive"))
    )
    (net (code "31") (name "/DRV11") (class "Default")
      (node (ref "Q11") (pin "1") (pinfunction "G_1") (pintype "passive"))
      (node (ref "R11") (pin "2") (pinfunction "2_2") (pintype "passive"))
    )
    (net (code "32") (name "/DRV12") (class "Default")
      (node (ref "Q12") (pin "1") (pinfunction "G_1") (pintype "passive"))
      (node (ref "R12") (pin "2") (pinfunction "2_2") (pintype "passive"))
    )
    (net (code "33") (name "/DRV13") (class "Default")
      (node (ref "Q13") (pin "1") (pinfunction "G_1") (pintype "passive"))
      (node (ref "R13") (pin "2") (pinfunction "2_2") (pintype "passive"))
    )
    (net (code "34") (name "/DRV14") (class "Default")
      (node (ref "Q14") (pin "1") (pinfunction "G_1") (pintype "passive"))
      (node (ref "R14") (pin "2") (pinfunction "2_2") (pintype "passive"))
    )
    (net (code "35") (name "/DRV15") (class "Default")
      (node (ref "Q15") (pin "1") (pinfunction "G_1") (pintype "passive"))
      (node (ref "R15") (pin "2") (pinfunction "2_2") (pintype "passive"))
    )
    (net (code "36") (name "/DRV16") (class "Default")
      (node (ref "Q16") (pin "1") (pinfunction "G_1") (pintype "passive"))
      (node (ref "R16") (pin "2") (pinfunction "2_2") (pintype "passive"))
    )
    (net (code "37") (name "/DRV17") (class "Default")
      (node (ref "Q17") (pin "1") (pinfunction "G_1") (pintype "passive"))
      (node (ref "R17") (pin "2") (pinfunction "2_2") (pintype "passive"))
    )
    (net (code "38") (name "/DRV18") (class "Default")
      (node (ref "Q18") (pin "1") (pinfunction "G_1") (pintype "passive"))
      (node (ref "R18") (pin "2") (pinfunction "2_2") (pintype "passive"))
    )
    (net (code "39") (name "/DRV19") (class "Default")
      (node (ref "Q19") (pin "1") (pinfunction "G_1") (pintype "passive"))
      (node (ref "R19") (pin "2") (pinfunction "2_2") (pintype "passive"))
    )
    (net (code "40") (name "/DRV20") (class "Default")
      (node (ref "Q20") (pin "1") (pinfunction "G_1") (pintype "passive"))
      (node (ref "R20") (pin "2") (pinfunction "2_2") (pintype "passive"))
    )
    (net (code "41") (name "/DRV21") (class "Default")
      (node (ref "Q21") (pin "1") (pinfunction "G_1") (pintype "passive"))
      (node (ref "R21") (pin "2") (pinfunction "2_2") (pintype "passive"))
    )
    (net (code "42") (name "/DRV22") (class "Default")
      (node (ref "Q22") (pin "1") (pinfunction "G_1") (pintype "passive"))
      (node (ref "R22") (pin "2") (pinfunction "2_2") (pintype "passive"))
    )
    (net (code "43") (name "/DRV23") (class "Default")
      (node (ref "Q23") (pin "1") (pinfunction "G_1") (pintype "passive"))
      (node (ref "R23") (pin "2") (pinfunction "2_2") (pintype "passive"))
    )
    (net (code "44") (name "/DRV24") (class "Default")
      (node (ref "Q24") (pin "1") (pinfunction "G_1") (pintype "passive"))
      (node (ref "R24") (pin "2") (pinfunction "2_2") (pintype "passive"))
    )
    (net (code "45") (name "/DRV25") (class "Default")
      (node (ref "Q25") (pin "1") (pinfunction "G_1") (pintype "passive"))
      (node (ref "R25") (pin "2") (pinfunction "2_2") (pintype "passive"))
    )
    (net (code "46") (name "/DRV26") (class "Default")
      (node (ref "Q26") (pin "1") (pinfunction "G_1") (pintype "passive"))
      (node (ref "R26") (pin "2") (pinfunction "2_2") (pintype "passive"))
    )
    (net (code "47") (name "/DRV27") (class "Default")
      (node (ref "Q27") (pin "1") (pinfunction "G_1") (pintype "passive"))
      (node (ref "R27") (pin "2") (pinfunction "2_2") (pintype "passive"))
    )
    (net (code "48") (name "/DRV28") (class "Default")
      (node (ref "Q28") (pin "1") (pinfunction "G_1") (pintype "passive"))
      (node (ref "R28") (pin "2") (pinfunction "2_2") (pintype "passive"))
    )
    (net (code "49") (name "/DRV29") (class "Default")
      (node (ref "Q29") (pin "1") (pinfunction "G_1") (pintype "passive"))
      (node (ref "R29") (pin "2") (pinfunction "2_2") (pintype "passive"))
    )
    (net (code "50") (name "/DRV30") (class "Default")
      (node (ref "Q30") (pin "1") (pinfunction "G_1") (pintype "passive"))
      (node (ref "R30") (pin "2") (pinfunction "2_2") (pintype "passive"))
    )
    (net (code "51") (name "/DRV31") (class "Default")
      (node (ref "Q31") (pin "1") (pinfunction "G_1") (pintype "passive"))
      (node (ref "R31") (pin "2") (pinfunction "2_2") (pintype "passive"))
    )
    (net (code "52") (name "/DRV32") (class "Default")
      (node (ref "Q32") (pin "1") (pinfunction "G_1") (pintype "passive"))
      (node (ref "R32") (pin "2") (pinfunction "2_2") (pintype "passive"))
    )
    (net (code "53") (name "/DRV33") (class "Default")
      (node (ref "Q33") (pin "1") (pinfunction "G_1") (pintype "passive"))
      (node (ref "R33") (pin "2") (pinfunction "2_2") (pintype "passive"))
    )
    (net (code "54") (name "/DRV34") (class "Default")
      (node (ref "Q34") (pin "1") (pinfunction "G_1") (pintype "passive"))
      (node (ref "R34") (pin "2") (pinfunction "2_2") (pintype "passive"))
    )
    (net (code "55") (name "/DRV35") (class "Default")
      (node (ref "Q35") (pin "1") (pinfunction "G_1") (pintype "passive"))
      (node (ref "R35") (pin "2") (pinfunction "2_2") (pintype "passive"))
    )
    (net (code "56") (name "/DRV36") (class "Default")
      (node (ref "Q36") (pin "1") (pinfunction "G_1") (pintype "passive"))
      (node (ref "R36") (pin "2") (pinfunction "2_2") (pintype "passive"))
    )
    (net (code "57") (name "/DRV37") (class "Default")
      (node (ref "Q37") (pin "1") (pinfunction "G_1") (pintype "passive"))
      (node (ref "R37") (pin "2") (pinfunction "2_2") (pintype "passive"))
    )
    (net (code "58") (name "/DRV38") (class "Default")
      (node (ref "Q38") (pin "1") (pinfunction "G_1") (pintype "passive"))
      (node (ref "R38") (pin "2") (pinfunction "2_2") (pintype "passive"))
    )
    (net (code "59") (name "/DRV39") (class "Default")
      (node (ref "Q39") (pin "1") (pinfunction "G_1") (pintype "passive"))
      (node (ref "R39") (pin "2") (pinfunction "2_2") (pintype "passive"))
    )
    (net (code "60") (name "/DRV40") (class "Default")
      (node (ref "Q40") (pin "1") (pinfunction "G_1") (pintype "passive"))
      (node (ref "R40") (pin "2") (pinfunction "2_2") (pintype "passive"))
    )
    (net (code "61") (name "/DRV41") (class "Default")
      (node (ref "Q41") (pin "1") (pinfunction "G_1") (pintype "passive"))
      (node (ref "R41") (pin "2") (pinfunction "2_2") (pintype "passive"))
    )
    (net (code "62") (name "/DRV42") (class "Default")
      (node (ref "Q42") (pin "1") (pinfunction "G_1") (pintype "passive"))
      (node (ref "R42") (pin "2") (pinfunction "2_2") (pintype "passive"))
    )
    (net (code "63") (name "/DRV43") (class "Default")
      (node (ref "Q43") (pin "1") (pinfunction "G_1") (pintype "passive"))
      (node (ref "R48") (pin "2") (pinfunction "2_2") (pintype "passive"))
    )
    (net (code "64") (name "/DRV44") (class "Default")
      (node (ref "Q44") (pin "1") (pinfunction "G_1") (pintype "passive"))
      (node (ref "R49") (pin "2") (pinfunction "2_2") (pintype "passive"))
    )
    (net (code "65") (name "/DRV45") (class "Default")
      (node (ref "Q45") (pin "1") (pinfunction "G_1") (pintype "passive"))
      (node (ref "R50") (pin "2") (pinfunction "2_2") (pintype "passive"))
    )
    (net (code "66") (name "/DRV46") (class "Default")
      (node (ref "Q46") (pin "1") (pinfunction "G_1") (pintype "passive"))
      (node (ref "R51") (pin "2") (pinfunction "2_2") (pintype "passive"))
    )
    (net (code "67") (name "/DRV47") (class "Default")
      (node (ref "Q47") (pin "1") (pinfunction "G_1") (pintype "passive"))
      (node (ref "R52") (pin "2") (pinfunction "2_2") (pintype "passive"))
    )
    (net (code "68") (name "/DRV48") (class "Default")
      (node (ref "Q48") (pin "1") (pinfunction "G_1") (pintype "passive"))
      (node (ref "R53") (pin "2") (pinfunction "2_2") (pintype "passive"))
    )
    (net (code "69") (name "/DRV49") (class "Default")
      (node (ref "Q49") (pin "1") (pinfunction "G_1") (pintype "passive"))
      (node (ref "R54") (pin "2") (pinfunction "2_2") (pintype "passive"))
    )
    (net (code "70") (name "/DRV50") (class "Default")
      (node (ref "Q50") (pin "1") (pinfunction "G_1") (pintype "passive"))
      (node (ref "R55") (pin "2") (pinfunction "2_2") (pintype "passive"))
    )
    (net (code "71") (name "/DRV51") (class "Default")
      (node (ref "Q51") (pin "1") (pinfunction "G_1") (pintype "passive"))
      (node (ref "R56") (pin "2") (pinfunction "2_2") (pintype "passive"))
    )
    (net (code "72") (name "/DRV52") (class "Default")
      (node (ref "Q52") (pin "1") (pinfunction "G_1") (pintype "passive"))
      (node (ref "R57") (pin "2") (pinfunction "2_2") (pintype "passive"))
    )
    (net (code "73") (name "/DRV53") (class "Default")
      (node (ref "Q53") (pin "1") (pinfunction "G_1") (pintype "passive"))
      (node (ref "R58") (pin "2") (pinfunction "2_2") (pintype "passive"))
    )
    (net (code "74") (name "/DRV54") (class "Default")
      (node (ref "Q54") (pin "1") (pinfunction "G_1") (pintype "passive"))
      (node (ref "R59") (pin "2") (pinfunction "2_2") (pintype "passive"))
    )
    (net (code "75") (name "/DRV55") (class "Default")
      (node (ref "Q55") (pin "1") (pinfunction "G_1") (pintype "passive"))
      (node (ref "R60") (pin "2") (pinfunction "2_2") (pintype "passive"))
    )
    (net (code "76") (name "/DRV56") (class "Default")
      (node (ref "Q56") (pin "1") (pinfunction "G_1") (pintype "passive"))
      (node (ref "R61") (pin "2") (pinfunction "2_2") (pintype "passive"))
    )
    (net (code "77") (name "/DRV57") (class "Default")
      (node (ref "Q57") (pin "1") (pinfunction "G_1") (pintype "passive"))
      (node (ref "R62") (pin "2") (pinfunction "2_2") (pintype "passive"))
    )
    (net (code "78") (name "/DRV58") (class "Default")
      (node (ref "Q58") (pin "1") (pinfunction "G_1") (pintype "passive"))
      (node (ref "R63") (pin "2") (pinfunction "2_2") (pintype "passive"))
    )
    (net (code "79") (name "/DRV59") (class "Default")
      (node (ref "Q59") (pin "1") (pinfunction "G_1") (pintype "passive"))
      (node (ref "R64") (pin "2") (pinfunction "2_2") (pintype "passive"))
    )
    (net (code "80") (name "/DRV60") (class "Default")
      (node (ref "Q60") (pin "1") (pinfunction "G_1") (pintype "passive"))
      (node (ref "R65") (pin "2") (pinfunction "2_2") (pintype "passive"))
    )
    (net (code "81") (name "/DRV61") (class "Default")
      (node (ref "Q61") (pin "1") (pinfunction "G_1") (pintype "passive"))
      (node (ref "R66") (pin "2") (pinfunction "2_2") (pintype "passive"))
    )
    (net (code "82") (name "/DRV62") (class "Default")
      (node (ref "Q62") (pin "1") (pinfunction "G_1") (pintype "passive"))
      (node (ref "R67") (pin "2") (pinfunction "2_2") (pintype "passive"))
    )
    (net (code "83") (name "/DRV63") (class "Default")
      (node (ref "Q63") (pin "1") (pinfunction "G_1") (pintype "passive"))
      (node (ref "R68") (pin "2") (pinfunction "2_2") (pintype "passive"))
    )
    (net (code "84") (name "/DRV64") (class "Default")
      (node (ref "Q64") (pin "1") (pinfunction "G_1") (pintype "passive"))
      (node (ref "R69") (pin "2") (pinfunction "2_2") (pintype "passive"))
    )
    (net (code "86") (name "/FUN") (class "Default")
      (node (ref "X4") (pin "A10") (pinfunction "A10_A10") (pintype "passive"))
    )
    (net (code "87") (name "/MISO") (class "Default")
      (node (ref "X4") (pin "A15") (pinfunction "A15_A15") (pintype "passive"))
    )
    (net (code "88") (name "/MOSI") (class "Default")
      (node (ref "X4") (pin "A14") (pinfunction "A14_A14") (pintype "passive"))
    )
    (net (code "89") (name "/RST") (class "Default")
      (node (ref "Q69") (pin "1") (pinfunction "G_1") (pintype "passive"))
      (node (ref "R130") (pin "2") (pinfunction "2_2") (pintype "passive"))
      (node (ref "X4") (pin "B10") (pinfunction "B10_B10") (pintype "passive"))
    )
    (net (code "90") (name "/SCLK") (class "Default")
      (node (ref "X4") (pin "B14") (pinfunction "B14_B14") (pintype "passive"))
    )
    (net (code "91") (name "/nPOR") (class "Default")
      (node (ref "Q69") (pin "3") (pinfunction "D_3") (pintype "passive"))
    )
    (net (code "99") (name "3V3IO") (class "Default")
      (node (ref "J12") (pin "1") (pinfunction "1_1") (pintype "passive"))
      (node (ref "R121") (pin "2") (pinfunction "2_2") (pintype "passive"))
    )
    (net (code "100") (name "5V0R") (class "Default")
      (node (ref "D12") (pin "1") (pinfunction "Anode_1") (pintype "passive"))
      (node (ref "K1") (pin "1") (pinfunction "+_1") (pintype "passive"))
      (node (ref "K10") (pin "1") (pinfunction "+_1") (pintype "passive"))
      (node (ref "K11") (pin "1") (pinfunction "+_1") (pintype "passive"))
      (node (ref "K12") (pin "1") (pinfunction "+_1") (pintype "passive"))
      (node (ref "K13") (pin "1") (pinfunction "+_1") (pintype "passive"))
      (node (ref "K14") (pin "1") (pinfunction "+_1") (pintype "passive"))
      (node (ref "K15") (pin "1") (pinfunction "+_1") (pintype "passive"))
      (node (ref "K16") (pin "1") (pinfunction "+_1") (pintype "passive"))
      (node (ref "K17") (pin "1") (pinfunction "+_1") (pintype "passive"))
      (node (ref "K18") (pin "1") (pinfunction "+_1") (pintype "passive"))
      (node (ref "K19") (pin "1") (pinfunction "+_1") (pintype "passive"))
      (node (ref "K2") (pin "1") (pinfunction "+_1") (pintype "passive"))
      (node (ref "K20") (pin "1") (pinfunction "+_1") (pintype "passive"))
      (node (ref "K21") (pin "1") (pinfunction "+_1") (pintype "passive"))
      (node (ref "K22") (pin "1") (pinfunction "+_1") (pintype "passive"))
      (node (ref "K23") (pin "1") (pinfunction "+_1") (pintype "passive"))
      (node (ref "K24") (pin "1") (pinfunction "+_1") (pintype "passive"))
      (node (ref "K25") (pin "1") (pinfunction "+_1") (pintype "passive"))
      (node (ref "K26") (pin "1") (pinfunction "+_1") (pintype "passive"))
      (node (ref "K27") (pin "1") (pinfunction "+_1") (pintype "passive"))
      (node (ref "K28") (pin "1") (pinfunction "+_1") (pintype "passive"))
      (node (ref "K29") (pin "1") (pinfunction "+_1") (pintype "passive"))
      (node (ref "K3") (pin "1") (pinfunction "+_1") (pintype "passive"))
      (node (ref "K30") (pin "1") (pinfunction "+_1") (pintype "passive"))
      (node (ref "K31") (pin "1") (pinfunction "+_1") (pintype "passive"))
      (node (ref "K32") (pin "1") (pinfunction "+_1") (pintype "passive"))
      (node (ref "K33") (pin "1") (pinfunction "+_1") (pintype "passive"))
      (node (ref "K34") (pin "1") (pinfunction "+_1") (pintype "passive"))
      (node (ref "K35") (pin "1") (pinfunction "+_1") (pintype "passive"))
      (node (ref "K36") (pin "1") (pinfunction "+_1") (pintype "passive"))
      (node (ref "K37") (pin "1") (pinfunction "+_1") (pintype "passive"))
      (node (ref "K38") (pin "1") (pinfunction "+_1") (pintype "passive"))
      (node (ref "K39") (pin "1") (pinfunction "+_1") (pintype "passive"))
      (node (ref "K4") (pin "1") (pinfunction "+_1") (pintype "passive"))
      (node (ref "K40") (pin "1") (pinfunction "+_1") (pintype "passive"))
      (node (ref "K41") (pin "1") (pinfunction "+_1") (pintype "passive"))
      (node (ref "K42") (pin "1") (pinfunction "+_1") (pintype "passive"))
      (node (ref "K43") (pin "1") (pinfunction "+_1") (pintype "passive"))
      (node (ref "K44") (pin "1") (pinfunction "+_1") (pintype "passive"))
      (node (ref "K45") (pin "1") (pinfunction "+_1") (pintype "passive"))
      (node (ref "K46") (pin "1") (pinfunction "+_1") (pintype "passive"))
      (node (ref "K47") (pin "1") (pinfunction "+_1") (pintype "passive"))
      (node (ref "K48") (pin "1") (pinfunction "+_1") (pintype "passive"))
      (node (ref "K49") (pin "1") (pinfunction "+_1") (pintype "passive"))
      (node (ref "K5") (pin "1") (pinfunction "+_1") (pintype "passive"))
      (node (ref "K50") (pin "1") (pinfunction "+_1") (pintype "passive"))
      (node (ref "K51") (pin "1") (pinfunction "+_1") (pintype "passive"))
      (node (ref "K52") (pin "1") (pinfunction "+_1") (pintype "passive"))
      (node (ref "K53") (pin "1") (pinfunction "+_1") (pintype "passive"))
      (node (ref "K54") (pin "1") (pinfunction "+_1") (pintype "passive"))
      (node (ref "K55") (pin "1") (pinfunction "+_1") (pintype "passive"))
      (node (ref "K56") (pin "1") (pinfunction "+_1") (pintype "passive"))
      (node (ref "K57") (pin "1") (pinfunction "+_1") (pintype "passive"))
      (node (ref "K58") (pin "1") (pinfunction "+_1") (pintype "passive"))
      (node (ref "K59") (pin "1") (pinfunction "+_1") (pintype "passive"))
      (node (ref "K6") (pin "1") (pinfunction "+_1") (pintype "passive"))
      (node (ref "K60") (pin "1") (pinfunction "+_1") (pintype "passive"))
      (node (ref "K61") (pin "1") (pinfunction "+_1") (pintype "passive"))
      (node (ref "K62") (pin "1") (pinfunction "+_1") (pintype "passive"))
      (node (ref "K63") (pin "1") (pinfunction "+_1") (pintype "passive"))
      (node (ref "K64") (pin "1") (pinfunction "+_1") (pintype "passive"))
      (node (ref "K7") (pin "1") (pinfunction "+_1") (pintype "passive"))
      (node (ref "K8") (pin "1") (pinfunction "+_1") (pintype "passive"))
      (node (ref "K9") (pin "1") (pinfunction "+_1") (pintype "passive"))
      (node (ref "TP5") (pin "1") (pinfunction "1_1") (pintype "passive"))
      (node (ref "X4") (pin "A7") (pinfunction "A7_A7") (pintype "passive"))
      (node (ref "X4") (pin "A8") (pinfunction "A8_A8") (pintype "passive"))
      (node (ref "X4") (pin "A9") (pinfunction "A9_A9") (pintype "passive"))
      (node (ref "X4") (pin "B7") (pinfunction "B7_B7") (pintype "passive"))
      (node (ref "X4") (pin "B8") (pinfunction "B8_B8") (pintype "passive"))
      (node (ref "X4") (pin "B9") (pinfunction "B9_B9") (pintype "passive"))
    )
    (net (code "101") (name "12V0") (class "Default")
      (node (ref "J11") (pin "1") (pinfunction "1_1") (pintype "passive"))
      (node (ref "TP6") (pin "1") (pinfunction "1_1") (pintype "passive"))
      (node (ref "X4") (pin "A11") (pinfunction "A11_A11") (pintype "passive"))
      (node (ref "X4") (pin "A12") (pinfunction "A12_A12") (pintype "passive"))
      (node (ref "X4") (pin "B11") (pinfunction "B11_B11") (pintype "passive"))
      (node (ref "X4") (pin "B12") (pinfunction "B12_B12") (pintype "passive"))
    )
    (net (code "102") (name "GND") (class "Default")
      (node (ref "J11") (pin "10") (pinfunction "10_10") (pintype "passive"))
      (node (ref "J11") (pin "2") (pinfunction "2_2") (pintype "passive"))
      (node (ref "J11") (pin "4") (pinfunction "4_4") (pintype "passive"))
      (node (ref "J11") (pin "6") (pinfunction "6_6") (pintype "passive"))
      (node (ref "J11") (pin "8") (pinfunction "8_8") (pintype "passive"))
      (node (ref "Q1") (pin "2") (pinfunction "S_2") (pintype "passive"))
      (node (ref "Q10") (pin "2") (pinfunction "S_2") (pintype "passive"))
      (node (ref "Q11") (pin "2") (pinfunction "S_2") (pintype "passive"))
      (node (ref "Q12") (pin "2") (pinfunction "S_2") (pintype "passive"))
      (node (ref "Q13") (pin "2") (pinfunction "S_2") (pintype "passive"))
      (node (ref "Q14") (pin "2") (pinfunction "S_2") (pintype "passive"))
      (node (ref "Q15") (pin "2") (pinfunction "S_2") (pintype "passive"))
      (node (ref "Q16") (pin "2") (pinfunction "S_2") (pintype "passive"))
      (node (ref "Q17") (pin "2") (pinfunction "S_2") (pintype "passive"))
      (node (ref "Q18") (pin "2") (pinfunction "S_2") (pintype "passive"))
      (node (ref "Q19") (pin "2") (pinfunction "S_2") (pintype "passive"))
      (node (ref "Q2") (pin "2") (pinfunction "S_2") (pintype "passive"))
      (node (ref "Q20") (pin "2") (pinfunction "S_2") (pintype "passive"))
      (node (ref "Q21") (pin "2") (pinfunction "S_2") (pintype "passive"))
      (node (ref "Q22") (pin "2") (pinfunction "S_2") (pintype "passive"))
      (node (ref "Q23") (pin "2") (pinfunction "S_2") (pintype "passive"))
      (node (ref "Q24") (pin "2") (pinfunction "S_2") (pintype "passive"))
      (node (ref "Q25") (pin "2") (pinfunction "S_2") (pintype "passive"))
      (node (ref "Q26") (pin "2") (pinfunction "S_2") (pintype "passive"))
      (node (ref "Q27") (pin "2") (pinfunction "S_2") (pintype "passive"))
      (node (ref "Q28") (pin "2") (pinfunction "S_2") (pintype "passive"))
      (node (ref "Q29") (pin "2") (pinfunction "S_2") (pintype "passive"))
      (node (ref "Q3") (pin "2") (pinfunction "S_2") (pintype "passive"))
      (node (ref "Q30") (pin "2") (pinfunction "S_2") (pintype "passive"))
      (node (ref "Q31") (pin "2") (pinfunction "S_2") (pintype "passive"))
      (node (ref "Q32") (pin "2") (pinfunction "S_2") (pintype "passive"))
      (node (ref "Q33") (pin "2") (pinfunction "S_2") (pintype "passive"))
      (node (ref "Q34") (pin "2") (pinfunction "S_2") (pintype "passive"))
      (node (ref "Q35") (pin "2") (pinfunction "S_2") (pintype "passive"))
      (node (ref "Q36") (pin "2") (pinfunction "S_2") (pintype "passive"))
      (node (ref "Q37") (pin "2") (pinfunction "S_2") (pintype "passive"))
      (node (ref "Q38") (pin "2") (pinfunction "S_2") (pintype "passive"))
      (node (ref "Q39") (pin "2") (pinfunction "S_2") (pintype "passive"))
      (node (ref "Q4") (pin "2") (pinfunction "S_2") (pintype "passive"))
      (node (ref "Q40") (pin "2") (pinfunction "S_2") (pintype "passive"))
      (node (ref "Q41") (pin "2") (pinfunction "S_2") (pintype "passive"))
      (node (ref "Q42") (pin "2") (pinfunction "S_2") (pintype "passive"))
      (node (ref "Q43") (pin "2") (pinfunction "S_2") (pintype "passive"))
      (node (ref "Q44") (pin "2") (pinfunction "S_2") (pintype "passive"))
      (node (ref "Q45") (pin "2") (pinfunction "S_2") (pintype "passive"))
      (node (ref "Q46") (pin "2") (pinfunction "S_2") (pintype "passive"))
      (node (ref "Q47") (pin "2") (pinfunction "S_2") (pintype "passive"))
      (node (ref "Q48") (pin "2") (pinfunction "S_2") (pintype "passive"))
      (node (ref "Q49") (pin "2") (pinfunction "S_2") (pintype "passive"))
      (node (ref "Q5") (pin "2") (pinfunction "S_2") (pintype "passive"))
      (node (ref "Q50") (pin "2") (pinfunction "S_2") (pintype "passive"))
      (node (ref "Q51") (pin "2") (pinfunction "S_2") (pintype "passive"))
      (node (ref "Q52") (pin "2") (pinfunction "S_2") (pintype "passive"))
      (node (ref "Q53") (pin "2") (pinfunction "S_2") (pintype "passive"))
      (node (ref "Q54") (pin "2") (pinfunction "S_2") (pintype "passive"))
      (node (ref "Q55") (pin "2") (pinfunction "S_2") (pintype "passive"))
      (node (ref "Q56") (pin "2") (pinfunction "S_2") (pintype "passive"))
      (node (ref "Q57") (pin "2") (pinfunction "S_2") (pintype "passive"))
      (node (ref "Q58") (pin "2") (pinfunction "S_2") (pintype "passive"))
      (node (ref "Q59") (pin "2") (pinfunction "S_2") (pintype "passive"))
      (node (ref "Q6") (pin "2") (pinfunction "S_2") (pintype "passive"))
      (node (ref "Q60") (pin "2") (pinfunction "S_2") (pintype "passive"))
      (node (ref "Q61") (pin "2") (pinfunction "S_2") (pintype "passive"))
      (node (ref "Q62") (pin "2") (pinfunction "S_2") (pintype "passive"))
      (node (ref "Q63") (pin "2") (pinfunction "S_2") (pintype "passive"))
      (node (ref "Q64") (pin "2") (pinfunction "S_2") (pintype "passive"))
      (node (ref "Q69") (pin "2") (pinfunction "S_2") (pintype "passive"))
      (node (ref "Q7") (pin "2") (pinfunction "S_2") (pintype "passive"))
      (node (ref "Q8") (pin "2") (pinfunction "S_2") (pintype "passive"))
      (node (ref "Q9") (pin "2") (pinfunction "S_2") (pintype "passive"))
      (node (ref "R1") (pin "1") (pinfunction "1_1") (pintype "passive"))
      (node (ref "R10") (pin "1") (pinfunction "1_1") (pintype "passive"))
      (node (ref "R11") (pin "1") (pinfunction "1_1") (pintype "passive"))
      (node (ref "R12") (pin "1") (pinfunction "1_1") (pintype "passive"))
      (node (ref "R125") (pin "1") (pinfunction "1_1") (pintype "passive"))
      (node (ref "R13") (pin "1") (pinfunction "1_1") (pintype "passive"))
      (node (ref "R130") (pin "1") (pinfunction "1_1") (pintype "passive"))
      (node (ref "R14") (pin "1") (pinfunction "1_1") (pintype "passive"))
      (node (ref "R15") (pin "1") (pinfunction "1_1") (pintype "passive"))
      (node (ref "R16") (pin "1") (pinfunction "1_1") (pintype "passive"))
      (node (ref "R17") (pin "1") (pinfunction "1_1") (pintype "passive"))
      (node (ref "R18") (pin "1") (pinfunction "1_1") (pintype "passive"))
      (node (ref "R19") (pin "1") (pinfunction "1_1") (pintype "passive"))
      (node (ref "R2") (pin "1") (pinfunction "1_1") (pintype "passive"))
      (node (ref "R20") (pin "1") (pinfunction "1_1") (pintype "passive"))
      (node (ref "R21") (pin "1") (pinfunction "1_1") (pintype "passive"))
      (node (ref "R22") (pin "1") (pinfunction "1_1") (pintype "passive"))
      (node (ref "R23") (pin "1") (pinfunction "1_1") (pintype "passive"))
      (node (ref "R24") (pin "1") (pinfunction "1_1") (pintype "passive"))
      (node (ref "R25") (pin "1") (pinfunction "1_1") (pintype "passive"))
      (node (ref "R26") (pin "1") (pinfunction "1_1") (pintype "passive"))
      (node (ref "R27") (pin "1") (pinfunction "1_1") (pintype "passive"))
      (node (ref "R28") (pin "1") (pinfunction "1_1") (pintype "passive"))
      (node (ref "R29") (pin "1") (pinfunction "1_1") (pintype "passive"))
      (node (ref "R3") (pin "1") (pinfunction "1_1") (pintype "passive"))
      (node (ref "R30") (pin "1") (pinfunction "1_1") (pintype "passive"))
      (node (ref "R31") (pin "1") (pinfunction "1_1") (pintype "passive"))
      (node (ref "R32") (pin "1") (pinfunction "1_1") (pintype "passive"))
      (node (ref "R33") (pin "1") (pinfunction "1_1") (pintype "passive"))
      (node (ref "R34") (pin "1") (pinfunction "1_1") (pintype "passive"))
      (node (ref "R35") (pin "1") (pinfunction "1_1") (pintype "passive"))
      (node (ref "R36") (pin "1") (pinfunction "1_1") (pintype "passive"))
      (node (ref "R37") (pin "1") (pinfunction "1_1") (pintype "passive"))
      (node (ref "R38") (pin "1") (pinfunction "1_1") (pintype "passive"))
      (node (ref "R39") (pin "1") (pinfunction "1_1") (pintype "passive"))
      (node (ref "R4") (pin "1") (pinfunction "1_1") (pintype "passive"))
      (node (ref "R40") (pin "1") (pinfunction "1_1") (pintype "passive"))
      (node (ref "R41") (pin "1") (pinfunction "1_1") (pintype "passive"))
      (node (ref "R42") (pin "1") (pinfunction "1_1") (pintype "passive"))
      (node (ref "R48") (pin "1") (pinfunction "1_1") (pintype "passive"))
      (node (ref "R49") (pin "1") (pinfunction "1_1") (pintype "passive"))
      (node (ref "R5") (pin "1") (pinfunction "1_1") (pintype "passive"))
      (node (ref "R50") (pin "1") (pinfunction "1_1") (pintype "passive"))
      (node (ref "R51") (pin "1") (pinfunction "1_1") (pintype "passive"))
      (node (ref "R52") (pin "1") (pinfunction "1_1") (pintype "passive"))
      (node (ref "R53") (pin "1") (pinfunction "1_1") (pintype "passive"))
      (node (ref "R54") (pin "1") (pinfunction "1_1") (pintype "passive"))
      (node (ref "R55") (pin "1") (pinfunction "1_1") (pintype "passive"))
      (node (ref "R56") (pin "1") (pinfunction "1_1") (pintype "passive"))
      (node (ref "R57") (pin "1") (pinfunction "1_1") (pintype "passive"))
      (node (ref "R58") (pin "1") (pinfunction "1_1") (pintype "passive"))
      (node (ref "R59") (pin "1") (pinfunction "1_1") (pintype "passive"))
      (node (ref "R6") (pin "1") (pinfunction "1_1") (pintype "passive"))
      (node (ref "R60") (pin "1") (pinfunction "1_1") (pintype "passive"))
      (node (ref "R61") (pin "1") (pinfunction "1_1") (pintype "passive"))
      (node (ref "R62") (pin "1") (pinfunction "1_1") (pintype "passive"))
      (node (ref "R63") (pin "1") (pinfunction "1_1") (pintype "passive"))
      (node (ref "R64") (pin "1") (pinfunction "1_1") (pintype "passive"))
      (node (ref "R65") (pin "1") (pinfunction "1_1") (pintype "passive"))
      (node (ref "R66") (pin "1") (pinfunction "1_1") (pintype "passive"))
      (node (ref "R67") (pin "1") (pinfunction "1_1") (pintype "passive"))
      (node (ref "R68") (pin "1") (pinfunction "1_1") (pintype "passive"))
      (node (ref "R69") (pin "1") (pinfunction "1_1") (pintype "passive"))
      (node (ref "R7") (pin "1") (pinfunction "1_1") (pintype "passive"))
      (node (ref "R8") (pin "1") (pinfunction "1_1") (pintype "passive"))
      (node (ref "R9") (pin "1") (pinfunction "1_1") (pintype "passive"))
      (node (ref "TP5") (pin "2") (pinfunction "2_2") (pintype "passive"))
      (node (ref "TP6") (pin "2") (pinfunction "2_2") (pintype "passive"))
      (node (ref "X4") (pin "A1") (pinfunction "A1_A1") (pintype "passive"))
      (node (ref "X4") (pin "A13") (pinfunction "A13_A13") (pintype "passive"))
      (node (ref "X4") (pin "A16") (pinfunction "A16_A16") (pintype "passive"))
      (node (ref "X4") (pin "A6") (pinfunction "A6_A6") (pintype "passive"))
      (node (ref "X4") (pin "B1") (pinfunction "B1_B1") (pintype "passive"))
      (node (ref "X4") (pin "B13") (pinfunction "B13_B13") (pintype "passive"))
      (node (ref "X4") (pin "B16") (pinfunction "B16_B16") (pintype "passive"))
      (node (ref "X4") (pin "B6") (pinfunction "B6_B6") (pintype "passive"))
    )
    (net (code "103") (name "Net-(D12-Cathode)") (class "Default")
      (node (ref "D12") (pin "2") (pinfunction "Cathode_2") (pintype "passive"))
      (node (ref "R125") (pin "2") (pinfunction "2_2") (pintype "passive"))
    )
    (net (code "104") (name "Net-(J11-Pad3)") (class "Default")
      (node (ref "J11") (pin "3") (pinfunction "3_3") (pintype "passive"))
      (node (ref "J12") (pin "2") (pinfunction "2_2") (pintype "passive"))
    )
    (net (code "105") (name "Net-(K1A-CA)") (class "Default")
      (node (ref "K1") (pin "3") (pinfunction "CA_3") (pintype "passive"))
      (node (ref "X3") (pin "1") (pinfunction "1_1") (pintype "passive"))
    )
    (net (code "106") (name "Net-(K1A-CB)") (class "Default")
      (node (ref "K1") (pin "4") (pinfunction "CB_4") (pintype "passive"))
      (node (ref "X2") (pin "1") (pinfunction "1_1") (pintype "passive"))
    )
    (net (code "107") (name "Net-(K1B--)") (class "Default")
      (node (ref "K1") (pin "2") (pinfunction "-_2") (pintype "passive"))
      (node (ref "Q1") (pin "3") (pinfunction "D_3") (pintype "passive"))
    )
    (net (code "108") (name "Net-(K2A-CA)") (class "Default")
      (node (ref "K2") (pin "3") (pinfunction "CA_3") (pintype "passive"))
      (node (ref "X3") (pin "2") (pinfunction "2_2") (pintype "passive"))
    )
    (net (code "109") (name "Net-(K2A-CB)") (class "Default")
      (node (ref "K2") (pin "4") (pinfunction "CB_4") (pintype "passive"))
      (node (ref "X2") (pin "2") (pinfunction "2_2") (pintype "passive"))
    )
    (net (code "110") (name "Net-(K2B--)") (class "Default")
      (node (ref "K2") (pin "2") (pinfunction "-_2") (pintype "passive"))
      (node (ref "Q2") (pin "3") (pinfunction "D_3") (pintype "passive"))
    )
    (net (code "111") (name "Net-(K3A-CA)") (class "Default")
      (node (ref "K3") (pin "3") (pinfunction "CA_3") (pintype "passive"))
      (node (ref "X3") (pin "3") (pinfunction "3_3") (pintype "passive"))
    )
    (net (code "112") (name "Net-(K3A-CB)") (class "Default")
      (node (ref "K3") (pin "4") (pinfunction "CB_4") (pintype "passive"))
      (node (ref "X2") (pin "3") (pinfunction "3_3") (pintype "passive"))
    )
    (net (code "113") (name "Net-(K3B--)") (class "Default")
      (node (ref "K3") (pin "2") (pinfunction "-_2") (pintype "passive"))
      (node (ref "Q3") (pin "3") (pinfunction "D_3") (pintype "passive"))
    )
    (net (code "114") (name "Net-(K4A-CA)") (class "Default")
      (node (ref "K4") (pin "3") (pinfunction "CA_3") (pintype "passive"))
      (node (ref "X3") (pin "4") (pinfunction "4_4") (pintype "passive"))
    )
    (net (code "115") (name "Net-(K4A-CB)") (class "Default")
      (node (ref "K4") (pin "4") (pinfunction "CB_4") (pintype "passive"))
      (node (ref "X2") (pin "4") (pinfunction "4_4") (pintype "passive"))
    )
    (net (code "116") (name "Net-(K4B--)") (class "Default")
      (node (ref "K4") (pin "2") (pinfunction "-_2") (pintype "passive"))
      (node (ref "Q4") (pin "3") (pinfunction "D_3") (pintype "passive"))
    )
    (net (code "117") (name "Net-(K5A-CA)") (class "Default")
      (node (ref "K5") (pin "3") (pinfunction "CA_3") (pintype "passive"))
      (node (ref "X3") (pin "5") (pinfunction "5_5") (pintype "passive"))
    )
    (net (code "118") (name "Net-(K5A-CB)") (class "Default")
      (node (ref "K5") (pin "4") (pinfunction "CB_4") (pintype "passive"))
      (node (ref "X2") (pin "5") (pinfunction "5_5") (pintype "passive"))
    )
    (net (code "119") (name "Net-(K5B--)") (class "Default")
      (node (ref "K5") (pin "2") (pinfunction "-_2") (pintype "passive"))
      (node (ref "Q5") (pin "3") (pinfunction "D_3") (pintype "passive"))
    )
    (net (code "120") (name "Net-(K6A-CA)") (class "Default")
      (node (ref "K6") (pin "3") (pinfunction "CA_3") (pintype "passive"))
      (node (ref "X3") (pin "6") (pinfunction "6_6") (pintype "passive"))
    )
    (net (code "121") (name "Net-(K6A-CB)") (class "Default")
      (node (ref "K6") (pin "4") (pinfunction "CB_4") (pintype "passive"))
      (node (ref "X2") (pin "6") (pinfunction "6_6") (pintype "passive"))
    )
    (net (code "122") (name "Net-(K6B--)") (class "Default")
      (node (ref "K6") (pin "2") (pinfunction "-_2") (pintype "passive"))
      (node (ref "Q6") (pin "3") (pinfunction "D_3") (pintype "passive"))
    )
    (net (code "123") (name "Net-(K7A-CA)") (class "Default")
      (node (ref "K7") (pin "3") (pinfunction "CA_3") (pintype "passive"))
      (node (ref "X3") (pin "7") (pinfunction "7_7") (pintype "passive"))
    )
    (net (code "124") (name "Net-(K7A-CB)") (class "Default")
      (node (ref "K7") (pin "4") (pinfunction "CB_4") (pintype "passive"))
      (node (ref "X2") (pin "7") (pinfunction "7_7") (pintype "passive"))
    )
    (net (code "125") (name "Net-(K7B--)") (class "Default")
      (node (ref "K7") (pin "2") (pinfunction "-_2") (pintype "passive"))
      (node (ref "Q7") (pin "3") (pinfunction "D_3") (pintype "passive"))
    )
    (net (code "126") (name "Net-(K8A-CA)") (class "Default")
      (node (ref "K8") (pin "3") (pinfunction "CA_3") (pintype "passive"))
      (node (ref "X3") (pin "8") (pinfunction "8_8") (pintype "passive"))
    )
    (net (code "127") (name "Net-(K8A-CB)") (class "Default")
      (node (ref "K8") (pin "4") (pinfunction "CB_4") (pintype "passive"))
      (node (ref "X2") (pin "8") (pinfunction "8_8") (pintype "passive"))
    )
    (net (code "128") (name "Net-(K8B--)") (class "Default")
      (node (ref "K8") (pin "2") (pinfunction "-_2") (pintype "passive"))
      (node (ref "Q8") (pin "3") (pinfunction "D_3") (pintype "passive"))
    )
    (net (code "129") (name "Net-(K9A-CA)") (class "Default")
      (node (ref "K9") (pin "3") (pinfunction "CA_3") (pintype "passive"))
      (node (ref "X3") (pin "9") (pinfunction "9_9") (pintype "passive"))
    )
    (net (code "130") (name "Net-(K9A-CB)") (class "Default")
      (node (ref "K9") (pin "4") (pinfunction "CB_4") (pintype "passive"))
      (node (ref "X2") (pin "9") (pinfunction "9_9") (pintype "passive"))
    )
    (net (code "131") (name "Net-(K9B--)") (class "Default")
      (node (ref "K9") (pin "2") (pinfunction "-_2") (pintype "passive"))
      (node (ref "Q9") (pin "3") (pinfunction "D_3") (pintype "passive"))
    )
    (net (code "132") (name "Net-(K10A-CA)") (class "Default")
      (node (ref "K10") (pin "3") (pinfunction "CA_3") (pintype "passive"))
      (node (ref "X3") (pin "10") (pinfunction "10_10") (pintype "passive"))
    )
    (net (code "133") (name "Net-(K10A-CB)") (class "Default")
      (node (ref "K10") (pin "4") (pinfunction "CB_4") (pintype "passive"))
      (node (ref "X2") (pin "10") (pinfunction "10_10") (pintype "passive"))
    )
    (net (code "134") (name "Net-(K10B--)") (class "Default")
      (node (ref "K10") (pin "2") (pinfunction "-_2") (pintype "passive"))
      (node (ref "Q10") (pin "3") (pinfunction "D_3") (pintype "passive"))
    )
    (net (code "135") (name "Net-(K11A-CA)") (class "Default")
      (node (ref "K11") (pin "3") (pinfunction "CA_3") (pintype "passive"))
      (node (ref "X3") (pin "11") (pinfunction "11_11") (pintype "passive"))
    )
    (net (code "136") (name "Net-(K11A-CB)") (class "Default")
      (node (ref "K11") (pin "4") (pinfunction "CB_4") (pintype "passive"))
      (node (ref "X2") (pin "11") (pinfunction "11_11") (pintype "passive"))
    )
    (net (code "137") (name "Net-(K11B--)") (class "Default")
      (node (ref "K11") (pin "2") (pinfunction "-_2") (pintype "passive"))
      (node (ref "Q11") (pin "3") (pinfunction "D_3") (pintype "passive"))
    )
    (net (code "138") (name "Net-(K12A-CA)") (class "Default")
      (node (ref "K12") (pin "3") (pinfunction "CA_3") (pintype "passive"))
      (node (ref "X3") (pin "12") (pinfunction "12_12") (pintype "passive"))
    )
    (net (code "139") (name "Net-(K12A-CB)") (class "Default")
      (node (ref "K12") (pin "4") (pinfunction "CB_4") (pintype "passive"))
      (node (ref "X2") (pin "12") (pinfunction "12_12") (pintype "passive"))
    )
    (net (code "140") (name "Net-(K12B--)") (class "Default")
      (node (ref "K12") (pin "2") (pinfunction "-_2") (pintype "passive"))
      (node (ref "Q12") (pin "3") (pinfunction "D_3") (pintype "passive"))
    )
    (net (code "141") (name "Net-(K13A-CA)") (class "Default")
      (node (ref "K13") (pin "3") (pinfunction "CA_3") (pintype "passive"))
      (node (ref "X3") (pin "13") (pinfunction "13_13") (pintype "passive"))
    )
    (net (code "142") (name "Net-(K13A-CB)") (class "Default")
      (node (ref "K13") (pin "4") (pinfunction "CB_4") (pintype "passive"))
      (node (ref "X2") (pin "13") (pinfunction "13_13") (pintype "passive"))
    )
    (net (code "143") (name "Net-(K13B--)") (class "Default")
      (node (ref "K13") (pin "2") (pinfunction "-_2") (pintype "passive"))
      (node (ref "Q13") (pin "3") (pinfunction "D_3") (pintype "passive"))
    )
    (net (code "144") (name "Net-(K14A-CA)") (class "Default")
      (node (ref "K14") (pin "3") (pinfunction "CA_3") (pintype "passive"))
      (node (ref "X3") (pin "14") (pinfunction "14_14") (pintype "passive"))
    )
    (net (code "145") (name "Net-(K14A-CB)") (class "Default")
      (node (ref "K14") (pin "4") (pinfunction "CB_4") (pintype "passive"))
      (node (ref "X2") (pin "14") (pinfunction "14_14") (pintype "passive"))
    )
    (net (code "146") (name "Net-(K14B--)") (class "Default")
      (node (ref "K14") (pin "2") (pinfunction "-_2") (pintype "passive"))
      (node (ref "Q14") (pin "3") (pinfunction "D_3") (pintype "passive"))
    )
    (net (code "147") (name "Net-(K15A-CA)") (class "Default")
      (node (ref "K15") (pin "3") (pinfunction "CA_3") (pintype "passive"))
      (node (ref "X3") (pin "15") (pinfunction "15_15") (pintype "passive"))
    )
    (net (code "148") (name "Net-(K15A-CB)") (class "Default")
      (node (ref "K15") (pin "4") (pinfunction "CB_4") (pintype "passive"))
      (node (ref "X2") (pin "15") (pinfunction "15_15") (pintype "passive"))
    )
    (net (code "149") (name "Net-(K15B--)") (class "Default")
      (node (ref "K15") (pin "2") (pinfunction "-_2") (pintype "passive"))
      (node (ref "Q15") (pin "3") (pinfunction "D_3") (pintype "passive"))
    )
    (net (code "150") (name "Net-(K16A-CA)") (class "Default")
      (node (ref "K16") (pin "3") (pinfunction "CA_3") (pintype "passive"))
      (node (ref "X3") (pin "16") (pinfunction "16_16") (pintype "passive"))
    )
    (net (code "151") (name "Net-(K16A-CB)") (class "Default")
      (node (ref "K16") (pin "4") (pinfunction "CB_4") (pintype "passive"))
      (node (ref "X2") (pin "16") (pinfunction "16_16") (pintype "passive"))
    )
    (net (code "152") (name "Net-(K16B--)") (class "Default")
      (node (ref "K16") (pin "2") (pinfunction "-_2") (pintype "passive"))
      (node (ref "Q16") (pin "3") (pinfunction "D_3") (pintype "passive"))
    )
    (net (code "153") (name "Net-(K17A-CA)") (class "Default")
      (node (ref "K17") (pin "3") (pinfunction "CA_3") (pintype "passive"))
      (node (ref "X3") (pin "17") (pinfunction "17_17") (pintype "passive"))
    )
    (net (code "154") (name "Net-(K17A-CB)") (class "Default")
      (node (ref "K17") (pin "4") (pinfunction "CB_4") (pintype "passive"))
      (node (ref "X2") (pin "17") (pinfunction "17_17") (pintype "passive"))
    )
    (net (code "155") (name "Net-(K17B--)") (class "Default")
      (node (ref "K17") (pin "2") (pinfunction "-_2") (pintype "passive"))
      (node (ref "Q17") (pin "3") (pinfunction "D_3") (pintype "passive"))
    )
    (net (code "156") (name "Net-(K18A-CA)") (class "Default")
      (node (ref "K18") (pin "3") (pinfunction "CA_3") (pintype "passive"))
      (node (ref "X3") (pin "18") (pinfunction "18_18") (pintype "passive"))
    )
    (net (code "157") (name "Net-(K18A-CB)") (class "Default")
      (node (ref "K18") (pin "4") (pinfunction "CB_4") (pintype "passive"))
      (node (ref "X2") (pin "18") (pinfunction "18_18") (pintype "passive"))
    )
    (net (code "158") (name "Net-(K18B--)") (class "Default")
      (node (ref "K18") (pin "2") (pinfunction "-_2") (pintype "passive"))
      (node (ref "Q18") (pin "3") (pinfunction "D_3") (pintype "passive"))
    )
    (net (code "159") (name "Net-(K19A-CA)") (class "Default")
      (node (ref "K19") (pin "3") (pinfunction "CA_3") (pintype "passive"))
      (node (ref "X3") (pin "19") (pinfunction "19_19") (pintype "passive"))
    )
    (net (code "160") (name "Net-(K19A-CB)") (class "Default")
      (node (ref "K19") (pin "4") (pinfunction "CB_4") (pintype "passive"))
      (node (ref "X2") (pin "19") (pinfunction "19_19") (pintype "passive"))
    )
    (net (code "161") (name "Net-(K19B--)") (class "Default")
      (node (ref "K19") (pin "2") (pinfunction "-_2") (pintype "passive"))
      (node (ref "Q19") (pin "3") (pinfunction "D_3") (pintype "passive"))
    )
    (net (code "162") (name "Net-(K20A-CA)") (class "Default")
      (node (ref "K20") (pin "3") (pinfunction "CA_3") (pintype "passive"))
      (node (ref "X3") (pin "20") (pinfunction "20_20") (pintype "passive"))
    )
    (net (code "163") (name "Net-(K20A-CB)") (class "Default")
      (node (ref "K20") (pin "4") (pinfunction "CB_4") (pintype "passive"))
      (node (ref "X2") (pin "20") (pinfunction "20_20") (pintype "passive"))
    )
    (net (code "164") (name "Net-(K20B--)") (class "Default")
      (node (ref "K20") (pin "2") (pinfunction "-_2") (pintype "passive"))
      (node (ref "Q20") (pin "3") (pinfunction "D_3") (pintype "passive"))
    )
    (net (code "165") (name "Net-(K21A-CA)") (class "Default")
      (node (ref "K21") (pin "3") (pinfunction "CA_3") (pintype "passive"))
      (node (ref "X3") (pin "21") (pinfunction "21_21") (pintype "passive"))
    )
    (net (code "166") (name "Net-(K21A-CB)") (class "Default")
      (node (ref "K21") (pin "4") (pinfunction "CB_4") (pintype "passive"))
      (node (ref "X2") (pin "21") (pinfunction "21_21") (pintype "passive"))
    )
    (net (code "167") (name "Net-(K21B--)") (class "Default")
      (node (ref "K21") (pin "2") (pinfunction "-_2") (pintype "passive"))
      (node (ref "Q21") (pin "3") (pinfunction "D_3") (pintype "passive"))
    )
    (net (code "168") (name "Net-(K22A-CA)") (class "Default")
      (node (ref "K22") (pin "3") (pinfunction "CA_3") (pintype "passive"))
      (node (ref "X3") (pin "22") (pinfunction "22_22") (pintype "passive"))
    )
    (net (code "169") (name "Net-(K22A-CB)") (class "Default")
      (node (ref "K22") (pin "4") (pinfunction "CB_4") (pintype "passive"))
      (node (ref "X2") (pin "22") (pinfunction "22_22") (pintype "passive"))
    )
    (net (code "170") (name "Net-(K22B--)") (class "Default")
      (node (ref "K22") (pin "2") (pinfunction "-_2") (pintype "passive"))
      (node (ref "Q22") (pin "3") (pinfunction "D_3") (pintype "passive"))
    )
    (net (code "171") (name "Net-(K23A-CA)") (class "Default")
      (node (ref "K23") (pin "3") (pinfunction "CA_3") (pintype "passive"))
      (node (ref "X3") (pin "23") (pinfunction "23_23") (pintype "passive"))
    )
    (net (code "172") (name "Net-(K23A-CB)") (class "Default")
      (node (ref "K23") (pin "4") (pinfunction "CB_4") (pintype "passive"))
      (node (ref "X2") (pin "23") (pinfunction "23_23") (pintype "passive"))
    )
    (net (code "173") (name "Net-(K23B--)") (class "Default")
      (node (ref "K23") (pin "2") (pinfunction "-_2") (pintype "passive"))
      (node (ref "Q23") (pin "3") (pinfunction "D_3") (pintype "passive"))
    )
    (net (code "174") (name "Net-(K24A-CA)") (class "Default")
      (node (ref "K24") (pin "3") (pinfunction "CA_3") (pintype "passive"))
      (node (ref "X3") (pin "24") (pinfunction "24_24") (pintype "passive"))
    )
    (net (code "175") (name "Net-(K24A-CB)") (class "Default")
      (node (ref "K24") (pin "4") (pinfunction "CB_4") (pintype "passive"))
      (node (ref "X2") (pin "24") (pinfunction "24_24") (pintype "passive"))
    )
    (net (code "176") (name "Net-(K24B--)") (class "Default")
      (node (ref "K24") (pin "2") (pinfunction "-_2") (pintype "passive"))
      (node (ref "Q24") (pin "3") (pinfunction "D_3") (pintype "passive"))
    )
    (net (code "177") (name "Net-(K25A-CA)") (class "Default")
      (node (ref "K25") (pin "3") (pinfunction "CA_3") (pintype "passive"))
      (node (ref "X3") (pin "25") (pinfunction "25_25") (pintype "passive"))
    )
    (net (code "178") (name "Net-(K25A-CB)") (class "Default")
      (node (ref "K25") (pin "4") (pinfunction "CB_4") (pintype "passive"))
      (node (ref "X2") (pin "25") (pinfunction "25_25") (pintype "passive"))
    )
    (net (code "179") (name "Net-(K25B--)") (class "Default")
      (node (ref "K25") (pin "2") (pinfunction "-_2") (pintype "passive"))
      (node (ref "Q25") (pin "3") (pinfunction "D_3") (pintype "passive"))
    )
    (net (code "180") (name "Net-(K26A-CA)") (class "Default")
      (node (ref "K26") (pin "3") (pinfunction "CA_3") (pintype "passive"))
      (node (ref "X3") (pin "26") (pinfunction "26_26") (pintype "passive"))
    )
    (net (code "181") (name "Net-(K26A-CB)") (class "Default")
      (node (ref "K26") (pin "4") (pinfunction "CB_4") (pintype "passive"))
      (node (ref "X2") (pin "26") (pinfunction "26_26") (pintype "passive"))
    )
    (net (code "182") (name "Net-(K26B--)") (class "Default")
      (node (ref "K26") (pin "2") (pinfunction "-_2") (pintype "passive"))
      (node (ref "Q26") (pin "3") (pinfunction "D_3") (pintype "passive"))
    )
    (net (code "183") (name "Net-(K27A-CA)") (class "Default")
      (node (ref "K27") (pin "3") (pinfunction "CA_3") (pintype "passive"))
      (node (ref "X3") (pin "27") (pinfunction "27_27") (pintype "passive"))
    )
    (net (code "184") (name "Net-(K27A-CB)") (class "Default")
      (node (ref "K27") (pin "4") (pinfunction "CB_4") (pintype "passive"))
      (node (ref "X2") (pin "27") (pinfunction "27_27") (pintype "passive"))
    )
    (net (code "185") (name "Net-(K27B--)") (class "Default")
      (node (ref "K27") (pin "2") (pinfunction "-_2") (pintype "passive"))
      (node (ref "Q27") (pin "3") (pinfunction "D_3") (pintype "passive"))
    )
    (net (code "186") (name "Net-(K28A-CA)") (class "Default")
      (node (ref "K28") (pin "3") (pinfunction "CA_3") (pintype "passive"))
      (node (ref "X3") (pin "28") (pinfunction "28_28") (pintype "passive"))
    )
    (net (code "187") (name "Net-(K28A-CB)") (class "Default")
      (node (ref "K28") (pin "4") (pinfunction "CB_4") (pintype "passive"))
      (node (ref "X2") (pin "28") (pinfunction "28_28") (pintype "passive"))
    )
    (net (code "188") (name "Net-(K28B--)") (class "Default")
      (node (ref "K28") (pin "2") (pinfunction "-_2") (pintype "passive"))
      (node (ref "Q28") (pin "3") (pinfunction "D_3") (pintype "passive"))
    )
    (net (code "189") (name "Net-(K29A-CA)") (class "Default")
      (node (ref "K29") (pin "3") (pinfunction "CA_3") (pintype "passive"))
      (node (ref "X3") (pin "29") (pinfunction "29_29") (pintype "passive"))
    )
    (net (code "190") (name "Net-(K29A-CB)") (class "Default")
      (node (ref "K29") (pin "4") (pinfunction "CB_4") (pintype "passive"))
      (node (ref "X2") (pin "29") (pinfunction "29_29") (pintype "passive"))
    )
    (net (code "191") (name "Net-(K29B--)") (class "Default")
      (node (ref "K29") (pin "2") (pinfunction "-_2") (pintype "passive"))
      (node (ref "Q29") (pin "3") (pinfunction "D_3") (pintype "passive"))
    )
    (net (code "192") (name "Net-(K30A-CA)") (class "Default")
      (node (ref "K30") (pin "3") (pinfunction "CA_3") (pintype "passive"))
      (node (ref "X3") (pin "30") (pinfunction "30_30") (pintype "passive"))
    )
    (net (code "193") (name "Net-(K30A-CB)") (class "Default")
      (node (ref "K30") (pin "4") (pinfunction "CB_4") (pintype "passive"))
      (node (ref "X2") (pin "30") (pinfunction "30_30") (pintype "passive"))
    )
    (net (code "194") (name "Net-(K30B--)") (class "Default")
      (node (ref "K30") (pin "2") (pinfunction "-_2") (pintype "passive"))
      (node (ref "Q30") (pin "3") (pinfunction "D_3") (pintype "passive"))
    )
    (net (code "195") (name "Net-(K31A-CA)") (class "Default")
      (node (ref "K31") (pin "3") (pinfunction "CA_3") (pintype "passive"))
      (node (ref "X3") (pin "31") (pinfunction "31_31") (pintype "passive"))
    )
    (net (code "196") (name "Net-(K31A-CB)") (class "Default")
      (node (ref "K31") (pin "4") (pinfunction "CB_4") (pintype "passive"))
      (node (ref "X2") (pin "31") (pinfunction "31_31") (pintype "passive"))
    )
    (net (code "197") (name "Net-(K31B--)") (class "Default")
      (node (ref "K31") (pin "2") (pinfunction "-_2") (pintype "passive"))
      (node (ref "Q31") (pin "3") (pinfunction "D_3") (pintype "passive"))
    )
    (net (code "198") (name "Net-(K32A-CA)") (class "Default")
      (node (ref "K32") (pin "3") (pinfunction "CA_3") (pintype "passive"))
      (node (ref "X3") (pin "32") (pinfunction "32_32") (pintype "passive"))
    )
    (net (code "199") (name "Net-(K32A-CB)") (class "Default")
      (node (ref "K32") (pin "4") (pinfunction "CB_4") (pintype "passive"))
      (node (ref "X2") (pin "32") (pinfunction "32_32") (pintype "passive"))
    )
    (net (code "200") (name "Net-(K32B--)") (class "Default")
      (node (ref "K32") (pin "2") (pinfunction "-_2") (pintype "passive"))
      (node (ref "Q32") (pin "3") (pinfunction "D_3") (pintype "passive"))
    )
    (net (code "201") (name "Net-(K33A-CA)") (class "Default")
      (node (ref "K33") (pin "3") (pinfunction "CA_3") (pintype "passive"))
      (node (ref "X3") (pin "33") (pinfunction "33_33") (pintype "passive"))
    )
    (net (code "202") (name "Net-(K33A-CB)") (class "Default")
      (node (ref "K33") (pin "4") (pinfunction "CB_4") (pintype "passive"))
      (node (ref "X2") (pin "33") (pinfunction "33_33") (pintype "passive"))
    )
    (net (code "203") (name "Net-(K33B--)") (class "Default")
      (node (ref "K33") (pin "2") (pinfunction "-_2") (pintype "passive"))
      (node (ref "Q33") (pin "3") (pinfunction "D_3") (pintype "passive"))
    )
    (net (code "204") (name "Net-(K34A-CA)") (class "Default")
      (node (ref "K34") (pin "3") (pinfunction "CA_3") (pintype "passive"))
      (node (ref "X3") (pin "34") (pinfunction "34_34") (pintype "passive"))
    )
    (net (code "205") (name "Net-(K34A-CB)") (class "Default")
      (node (ref "K34") (pin "4") (pinfunction "CB_4") (pintype "passive"))
      (node (ref "X2") (pin "34") (pinfunction "34_34") (pintype "passive"))
    )
    (net (code "206") (name "Net-(K34B--)") (class "Default")
      (node (ref "K34") (pin "2") (pinfunction "-_2") (pintype "passive"))
      (node (ref "Q34") (pin "3") (pinfunction "D_3") (pintype "passive"))
    )
    (net (code "207") (name "Net-(K35A-CA)") (class "Default")
      (node (ref "K35") (pin "3") (pinfunction "CA_3") (pintype "passive"))
      (node (ref "X3") (pin "35") (pinfunction "35_35") (pintype "passive"))
    )
    (net (code "208") (name "Net-(K35A-CB)") (class "Default")
      (node (ref "K35") (pin "4") (pinfunction "CB_4") (pintype "passive"))
      (node (ref "X2") (pin "35") (pinfunction "35_35") (pintype "passive"))
    )
    (net (code "209") (name "Net-(K35B--)") (class "Default")
      (node (ref "K35") (pin "2") (pinfunction "-_2") (pintype "passive"))
      (node (ref "Q35") (pin "3") (pinfunction "D_3") (pintype "passive"))
    )
    (net (code "210") (name "Net-(K36A-CA)") (class "Default")
      (node (ref "K36") (pin "3") (pinfunction "CA_3") (pintype "passive"))
      (node (ref "X3") (pin "36") (pinfunction "36_36") (pintype "passive"))
    )
    (net (code "211") (name "Net-(K36A-CB)") (class "Default")
      (node (ref "K36") (pin "4") (pinfunction "CB_4") (pintype "passive"))
      (node (ref "X2") (pin "36") (pinfunction "36_36") (pintype "passive"))
    )
    (net (code "212") (name "Net-(K36B--)") (class "Default")
      (node (ref "K36") (pin "2") (pinfunction "-_2") (pintype "passive"))
      (node (ref "Q36") (pin "3") (pinfunction "D_3") (pintype "passive"))
    )
    (net (code "213") (name "Net-(K37A-CA)") (class "Default")
      (node (ref "K37") (pin "3") (pinfunction "CA_3") (pintype "passive"))
      (node (ref "X3") (pin "37") (pinfunction "37_37") (pintype "passive"))
    )
    (net (code "214") (name "Net-(K37A-CB)") (class "Default")
      (node (ref "K37") (pin "4") (pinfunction "CB_4") (pintype "passive"))
      (node (ref "X2") (pin "37") (pinfunction "37_37") (pintype "passive"))
    )
    (net (code "215") (name "Net-(K37B--)") (class "Default")
      (node (ref "K37") (pin "2") (pinfunction "-_2") (pintype "passive"))
      (node (ref "Q37") (pin "3") (pinfunction "D_3") (pintype "passive"))
    )
    (net (code "216") (name "Net-(K38A-CA)") (class "Default")
      (node (ref "K38") (pin "3") (pinfunction "CA_3") (pintype "passive"))
      (node (ref "X3") (pin "38") (pinfunction "38_38") (pintype "passive"))
    )
    (net (code "217") (name "Net-(K38A-CB)") (class "Default")
      (node (ref "K38") (pin "4") (pinfunction "CB_4") (pintype "passive"))
      (node (ref "X2") (pin "38") (pinfunction "38_38") (pintype "passive"))
    )
    (net (code "218") (name "Net-(K38B--)") (class "Default")
      (node (ref "K38") (pin "2") (pinfunction "-_2") (pintype "passive"))
      (node (ref "Q38") (pin "3") (pinfunction "D_3") (pintype "passive"))
    )
    (net (code "219") (name "Net-(K39A-CA)") (class "Default")
      (node (ref "K39") (pin "3") (pinfunction "CA_3") (pintype "passive"))
      (node (ref "X3") (pin "39") (pinfunction "39_39") (pintype "passive"))
    )
    (net (code "220") (name "Net-(K39A-CB)") (class "Default")
      (node (ref "K39") (pin "4") (pinfunction "CB_4") (pintype "passive"))
      (node (ref "X2") (pin "39") (pinfunction "39_39") (pintype "passive"))
    )
    (net (code "221") (name "Net-(K39B--)") (class "Default")
      (node (ref "K39") (pin "2") (pinfunction "-_2") (pintype "passive"))
      (node (ref "Q39") (pin "3") (pinfunction "D_3") (pintype "passive"))
    )
    (net (code "222") (name "Net-(K40A-CA)") (class "Default")
      (node (ref "K40") (pin "3") (pinfunction "CA_3") (pintype "passive"))
      (node (ref "X3") (pin "40") (pinfunction "40_40") (pintype "passive"))
    )
    (net (code "223") (name "Net-(K40A-CB)") (class "Default")
      (node (ref "K40") (pin "4") (pinfunction "CB_4") (pintype "passive"))
      (node (ref "X2") (pin "40") (pinfunction "40_40") (pintype "passive"))
    )
    (net (code "224") (name "Net-(K40B--)") (class "Default")
      (node (ref "K40") (pin "2") (pinfunction "-_2") (pintype "passive"))
      (node (ref "Q40") (pin "3") (pinfunction "D_3") (pintype "passive"))
    )
    (net (code "225") (name "Net-(K41A-CA)") (class "Default")
      (node (ref "K41") (pin "3") (pinfunction "CA_3") (pintype "passive"))
      (node (ref "X3") (pin "41") (pinfunction "41_41") (pintype "passive"))
    )
    (net (code "226") (name "Net-(K41A-CB)") (class "Default")
      (node (ref "K41") (pin "4") (pinfunction "CB_4") (pintype "passive"))
      (node (ref "X2") (pin "41") (pinfunction "41_41") (pintype "passive"))
    )
    (net (code "227") (name "Net-(K41B--)") (class "Default")
      (node (ref "K41") (pin "2") (pinfunction "-_2") (pintype "passive"))
      (node (ref "Q41") (pin "3") (pinfunction "D_3") (pintype "passive"))
    )
    (net (code "228") (name "Net-(K42A-CA)") (class "Default")
      (node (ref "K42") (pin "3") (pinfunction "CA_3") (pintype "passive"))
      (node (ref "X3") (pin "42") (pinfunction "42_42") (pintype "passive"))
    )
    (net (code "229") (name "Net-(K42A-CB)") (class "Default")
      (node (ref "K42") (pin "4") (pinfunction "CB_4") (pintype "passive"))
      (node (ref "X2") (pin "42") (pinfunction "42_42") (pintype "passive"))
    )
    (net (code "230") (name "Net-(K42B--)") (class "Default")
      (node (ref "K42") (pin "2") (pinfunction "-_2") (pintype "passive"))
      (node (ref "Q42") (pin "3") (pinfunction "D_3") (pintype "passive"))
    )
    (net (code "231") (name "Net-(K43A-CA)") (class "Default")
      (node (ref "K43") (pin "3") (pinfunction "CA_3") (pintype "passive"))
      (node (ref "X3") (pin "43") (pinfunction "43_43") (pintype "passive"))
    )
    (net (code "232") (name "Net-(K43A-CB)") (class "Default")
      (node (ref "K43") (pin "4") (pinfunction "CB_4") (pintype "passive"))
      (node (ref "X2") (pin "43") (pinfunction "43_43") (pintype "passive"))
    )
    (net (code "233") (name "Net-(K43B--)") (class "Default")
      (node (ref "K43") (pin "2") (pinfunction "-_2") (pintype "passive"))
      (node (ref "Q43") (pin "3") (pinfunction "D_3") (pintype "passive"))
    )
    (net (code "234") (name "Net-(K44A-CA)") (class "Default")
      (node (ref "K44") (pin "3") (pinfunction "CA_3") (pintype "passive"))
      (node (ref "X3") (pin "44") (pinfunction "44_44") (pintype "passive"))
    )
    (net (code "235") (name "Net-(K44A-CB)") (class "Default")
      (node (ref "K44") (pin "4") (pinfunction "CB_4") (pintype "passive"))
      (node (ref "X2") (pin "44") (pinfunction "44_44") (pintype "passive"))
    )
    (net (code "236") (name "Net-(K44B--)") (class "Default")
      (node (ref "K44") (pin "2") (pinfunction "-_2") (pintype "passive"))
      (node (ref "Q44") (pin "3") (pinfunction "D_3") (pintype "passive"))
    )
    (net (code "237") (name "Net-(K45A-CA)") (class "Default")
      (node (ref "K45") (pin "3") (pinfunction "CA_3") (pintype "passive"))
      (node (ref "X3") (pin "45") (pinfunction "45_45") (pintype "passive"))
    )
    (net (code "238") (name "Net-(K45A-CB)") (class "Default")
      (node (ref "K45") (pin "4") (pinfunction "CB_4") (pintype "passive"))
      (node (ref "X2") (pin "45") (pinfunction "45_45") (pintype "passive"))
    )
    (net (code "239") (name "Net-(K45B--)") (class "Default")
      (node (ref "K45") (pin "2") (pinfunction "-_2") (pintype "passive"))
      (node (ref "Q45") (pin "3") (pinfunction "D_3") (pintype "passive"))
    )
    (net (code "240") (name "Net-(K46A-CA)") (class "Default")
      (node (ref "K46") (pin "3") (pinfunction "CA_3") (pintype "passive"))
      (node (ref "X3") (pin "46") (pinfunction "46_46") (pintype "passive"))
    )
    (net (code "241") (name "Net-(K46A-CB)") (class "Default")
      (node (ref "K46") (pin "4") (pinfunction "CB_4") (pintype "passive"))
      (node (ref "X2") (pin "46") (pinfunction "46_46") (pintype "passive"))
    )
    (net (code "242") (name "Net-(K46B--)") (class "Default")
      (node (ref "K46") (pin "2") (pinfunction "-_2") (pintype "passive"))
      (node (ref "Q46") (pin "3") (pinfunction "D_3") (pintype "passive"))
    )
    (net (code "243") (name "Net-(K47A-CA)") (class "Default")
      (node (ref "K47") (pin "3") (pinfunction "CA_3") (pintype "passive"))
      (node (ref "X3") (pin "47") (pinfunction "47_47") (pintype "passive"))
    )
    (net (code "244") (name "Net-(K47A-CB)") (class "Default")
      (node (ref "K47") (pin "4") (pinfunction "CB_4") (pintype "passive"))
      (node (ref "X2") (pin "47") (pinfunction "47_47") (pintype "passive"))
    )
    (net (code "245") (name "Net-(K47B--)") (class "Default")
      (node (ref "K47") (pin "2") (pinfunction "-_2") (pintype "passive"))
      (node (ref "Q47") (pin "3") (pinfunction "D_3") (pintype "passive"))
    )
    (net (code "246") (name "Net-(K48A-CA)") (class "Default")
      (node (ref "K48") (pin "3") (pinfunction "CA_3") (pintype "passive"))
      (node (ref "X3") (pin "48") (pinfunction "48_48") (pintype "passive"))
    )
    (net (code "247") (name "Net-(K48A-CB)") (class "Default")
      (node (ref "K48") (pin "4") (pinfunction "CB_4") (pintype "passive"))
      (node (ref "X2") (pin "48") (pinfunction "48_48") (pintype "passive"))
    )
    (net (code "248") (name "Net-(K48B--)") (class "Default")
      (node (ref "K48") (pin "2") (pinfunction "-_2") (pintype "passive"))
      (node (ref "Q48") (pin "3") (pinfunction "D_3") (pintype "passive"))
    )
    (net (code "249") (name "Net-(K49A-CA)") (class "Default")
      (node (ref "K49") (pin "3") (pinfunction "CA_3") (pintype "passive"))
      (node (ref "X3") (pin "49") (pinfunction "49_49") (pintype "passive"))
    )
    (net (code "250") (name "Net-(K49A-CB)") (class "Default")
      (node (ref "K49") (pin "4") (pinfunction "CB_4") (pintype "passive"))
      (node (ref "X2") (pin "49") (pinfunction "49_49") (pintype "passive"))
    )
    (net (code "251") (name "Net-(K49B--)") (class "Default")
      (node (ref "K49") (pin "2") (pinfunction "-_2") (pintype "passive"))
      (node (ref "Q49") (pin "3") (pinfunction "D_3") (pintype "passive"))
    )
    (net (code "252") (name "Net-(K50A-CA)") (class "Default")
      (node (ref "K50") (pin "3") (pinfunction "CA_3") (pintype "passive"))
      (node (ref "X3") (pin "50") (pinfunction "50_50") (pintype "passive"))
    )
    (net (code "253") (name "Net-(K50A-CB)") (class "Default")
      (node (ref "K50") (pin "4") (pinfunction "CB_4") (pintype "passive"))
      (node (ref "X2") (pin "50") (pinfunction "50_50") (pintype "passive"))
    )
    (net (code "254") (name "Net-(K50B--)") (class "Default")
      (node (ref "K50") (pin "2") (pinfunction "-_2") (pintype "passive"))
      (node (ref "Q50") (pin "3") (pinfunction "D_3") (pintype "passive"))
    )
    (net (code "255") (name "Net-(K51A-CA)") (class "Default")
      (node (ref "K51") (pin "3") (pinfunction "CA_3") (pintype "passive"))
      (node (ref "X3") (pin "51") (pinfunction "51_51") (pintype "passive"))
    )
    (net (code "256") (name "Net-(K51A-CB)") (class "Default")
      (node (ref "K51") (pin "4") (pinfunction "CB_4") (pintype "passive"))
      (node (ref "X2") (pin "51") (pinfunction "51_51") (pintype "passive"))
    )
    (net (code "257") (name "Net-(K51B--)") (class "Default")
      (node (ref "K51") (pin "2") (pinfunction "-_2") (pintype "passive"))
      (node (ref "Q51") (pin "3") (pinfunction "D_3") (pintype "passive"))
    )
    (net (code "258") (name "Net-(K52A-CA)") (class "Default")
      (node (ref "K52") (pin "3") (pinfunction "CA_3") (pintype "passive"))
      (node (ref "X3") (pin "52") (pinfunction "52_52") (pintype "passive"))
    )
    (net (code "259") (name "Net-(K52A-CB)") (class "Default")
      (node (ref "K52") (pin "4") (pinfunction "CB_4") (pintype "passive"))
      (node (ref "X2") (pin "52") (pinfunction "52_52") (pintype "passive"))
    )
    (net (code "260") (name "Net-(K52B--)") (class "Default")
      (node (ref "K52") (pin "2") (pinfunction "-_2") (pintype "passive"))
      (node (ref "Q52") (pin "3") (pinfunction "D_3") (pintype "passive"))
    )
    (net (code "261") (name "Net-(K53A-CA)") (class "Default")
      (node (ref "K53") (pin "3") (pinfunction "CA_3") (pintype "passive"))
      (node (ref "X3") (pin "53") (pinfunction "53_53") (pintype "passive"))
    )
    (net (code "262") (name "Net-(K53A-CB)") (class "Default")
      (node (ref "K53") (pin "4") (pinfunction "CB_4") (pintype "passive"))
      (node (ref "X2") (pin "53") (pinfunction "53_53") (pintype "passive"))
    )
    (net (code "263") (name "Net-(K53B--)") (class "Default")
      (node (ref "K53") (pin "2") (pinfunction "-_2") (pintype "passive"))
      (node (ref "Q53") (pin "3") (pinfunction "D_3") (pintype "passive"))
    )
    (net (code "264") (name "Net-(K54A-CA)") (class "Default")
      (node (ref "K54") (pin "3") (pinfunction "CA_3") (pintype "passive"))
      (node (ref "X3") (pin "54") (pinfunction "54_54") (pintype "passive"))
    )
    (net (code "265") (name "Net-(K54A-CB)") (class "Default")
      (node (ref "K54") (pin "4") (pinfunction "CB_4") (pintype "passive"))
      (node (ref "X2") (pin "54") (pinfunction "54_54") (pintype "passive"))
    )
    (net (code "266") (name "Net-(K54B--)") (class "Default")
      (node (ref "K54") (pin "2") (pinfunction "-_2") (pintype "passive"))
      (node (ref "Q54") (pin "3") (pinfunction "D_3") (pintype "passive"))
    )
    (net (code "267") (name "Net-(K55A-CA)") (class "Default")
      (node (ref "K55") (pin "3") (pinfunction "CA_3") (pintype "passive"))
      (node (ref "X3") (pin "55") (pinfunction "55_55") (pintype "passive"))
    )
    (net (code "268") (name "Net-(K55A-CB)") (class "Default")
      (node (ref "K55") (pin "4") (pinfunction "CB_4") (pintype "passive"))
      (node (ref "X2") (pin "55") (pinfunction "55_55") (pintype "passive"))
    )
    (net (code "269") (name "Net-(K55B--)") (class "Default")
      (node (ref "K55") (pin "2") (pinfunction "-_2") (pintype "passive"))
      (node (ref "Q55") (pin "3") (pinfunction "D_3") (pintype "passive"))
    )
    (net (code "270") (name "Net-(K56A-CA)") (class "Default")
      (node (ref "K56") (pin "3") (pinfunction "CA_3") (pintype "passive"))
      (node (ref "X3") (pin "56") (pinfunction "56_56") (pintype "passive"))
    )
    (net (code "271") (name "Net-(K56A-CB)") (class "Default")
      (node (ref "K56") (pin "4") (pinfunction "CB_4") (pintype "passive"))
      (node (ref "X2") (pin "56") (pinfunction "56_56") (pintype "passive"))
    )
    (net (code "272") (name "Net-(K56B--)") (class "Default")
      (node (ref "K56") (pin "2") (pinfunction "-_2") (pintype "passive"))
      (node (ref "Q56") (pin "3") (pinfunction "D_3") (pintype "passive"))
    )
    (net (code "273") (name "Net-(K57A-CA)") (class "Default")
      (node (ref "K57") (pin "3") (pinfunction "CA_3") (pintype "passive"))
      (node (ref "X3") (pin "57") (pinfunction "57_57") (pintype "passive"))
    )
    (net (code "274") (name "Net-(K57A-CB)") (class "Default")
      (node (ref "K57") (pin "4") (pinfunction "CB_4") (pintype "passive"))
      (node (ref "X2") (pin "57") (pinfunction "57_57") (pintype "passive"))
    )
    (net (code "275") (name "Net-(K57B--)") (class "Default")
      (node (ref "K57") (pin "2") (pinfunction "-_2") (pintype "passive"))
      (node (ref "Q57") (pin "3") (pinfunction "D_3") (pintype "passive"))
    )
    (net (code "276") (name "Net-(K58A-CA)") (class "Default")
      (node (ref "K58") (pin "3") (pinfunction "CA_3") (pintype "passive"))
      (node (ref "X3") (pin "58") (pinfunction "58_58") (pintype "passive"))
    )
    (net (code "277") (name "Net-(K58A-CB)") (class "Default")
      (node (ref "K58") (pin "4") (pinfunction "CB_4") (pintype "passive"))
      (node (ref "X2") (pin "58") (pinfunction "58_58") (pintype "passive"))
    )
    (net (code "278") (name "Net-(K58B--)") (class "Default")
      (node (ref "K58") (pin "2") (pinfunction "-_2") (pintype "passive"))
      (node (ref "Q58") (pin "3") (pinfunction "D_3") (pintype "passive"))
    )
    (net (code "279") (name "Net-(K59A-CA)") (class "Default")
      (node (ref "K59") (pin "3") (pinfunction "CA_3") (pintype "passive"))
      (node (ref "X3") (pin "59") (pinfunction "59_59") (pintype "passive"))
    )
    (net (code "280") (name "Net-(K59A-CB)") (class "Default")
      (node (ref "K59") (pin "4") (pinfunction "CB_4") (pintype "passive"))
      (node (ref "X2") (pin "59") (pinfunction "59_59") (pintype "passive"))
    )
    (net (code "281") (name "Net-(K59B--)") (class "Default")
      (node (ref "K59") (pin "2") (pinfunction "-_2") (pintype "passive"))
      (node (ref "Q59") (pin "3") (pinfunction "D_3") (pintype "passive"))
    )
    (net (code "282") (name "Net-(K60A-CA)") (class "Default")
      (node (ref "K60") (pin "3") (pinfunction "CA_3") (pintype "passive"))
      (node (ref "X3") (pin "60") (pinfunction "60_60") (pintype "passive"))
    )
    (net (code "283") (name "Net-(K60A-CB)") (class "Default")
      (node (ref "K60") (pin "4") (pinfunction "CB_4") (pintype "passive"))
      (node (ref "X2") (pin "60") (pinfunction "60_60") (pintype "passive"))
    )
    (net (code "284") (name "Net-(K60B--)") (class "Default")
      (node (ref "K60") (pin "2") (pinfunction "-_2") (pintype "passive"))
      (node (ref "Q60") (pin "3") (pinfunction "D_3") (pintype "passive"))
    )
    (net (code "285") (name "Net-(K61A-CA)") (class "Default")
      (node (ref "K61") (pin "3") (pinfunction "CA_3") (pintype "passive"))
      (node (ref "X3") (pin "61") (pinfunction "61_61") (pintype "passive"))
    )
    (net (code "286") (name "Net-(K61A-CB)") (class "Default")
      (node (ref "K61") (pin "4") (pinfunction "CB_4") (pintype "passive"))
      (node (ref "X2") (pin "61") (pinfunction "61_61") (pintype "passive"))
    )
    (net (code "287") (name "Net-(K61B--)") (class "Default")
      (node (ref "K61") (pin "2") (pinfunction "-_2") (pintype "passive"))
      (node (ref "Q61") (pin "3") (pinfunction "D_3") (pintype "passive"))
    )
    (net (code "288") (name "Net-(K62A-CA)") (class "Default")
      (node (ref "K62") (pin "3") (pinfunction "CA_3") (pintype "passive"))
      (node (ref "X3") (pin "62") (pinfunction "62_62") (pintype "passive"))
    )
    (net (code "289") (name "Net-(K62A-CB)") (class "Default")
      (node (ref "K62") (pin "4") (pinfunction "CB_4") (pintype "passive"))
      (node (ref "X2") (pin "62") (pinfunction "62_62") (pintype "passive"))
    )
    (net (code "290") (name "Net-(K62B--)") (class "Default")
      (node (ref "K62") (pin "2") (pinfunction "-_2") (pintype "passive"))
      (node (ref "Q62") (pin "3") (pinfunction "D_3") (pintype "passive"))
    )
    (net (code "291") (name "Net-(K63A-CA)") (class "Default")
      (node (ref "K63") (pin "3") (pinfunction "CA_3") (pintype "passive"))
      (node (ref "X3") (pin "63") (pinfunction "63_63") (pintype "passive"))
    )
    (net (code "292") (name "Net-(K63A-CB)") (class "Default")
      (node (ref "K63") (pin "4") (pinfunction "CB_4") (pintype "passive"))
      (node (ref "X2") (pin "63") (pinfunction "63_63") (pintype "passive"))
    )
    (net (code "293") (name "Net-(K63B--)") (class "Default")
      (node (ref "K63") (pin "2") (pinfunction "-_2") (pintype "passive"))
      (node (ref "Q63") (pin "3") (pinfunction "D_3") (pintype "passive"))
    )
    (net (code "294") (name "Net-(K64A-CA)") (class "Default")
      (node (ref "K64") (pin "3") (pinfunction "CA_3") (pintype "passive"))
      (node (ref "X3") (pin "64") (pinfunction "64_64") (pintype "passive"))
    )
    (net (code "295") (name "Net-(K64A-CB)") (class "Default")
      (node (ref "K64") (pin "4") (pinfunction "CB_4") (pintype "passive"))
      (node (ref "X2") (pin "64") (pinfunction "64_64") (pintype "passive"))
    )
    (net (code "296") (name "Net-(K64B--)") (class "Default")
      (node (ref "K64") (pin "2") (pinfunction "-_2") (pintype "passive"))
      (node (ref "Q64") (pin "3") (pinfunction "D_3") (pintype "passive"))
    )
  )
)
